# FPGA_2_MICS_SUP.net
KiCad netlist of a schematic drawn in Altium Designer
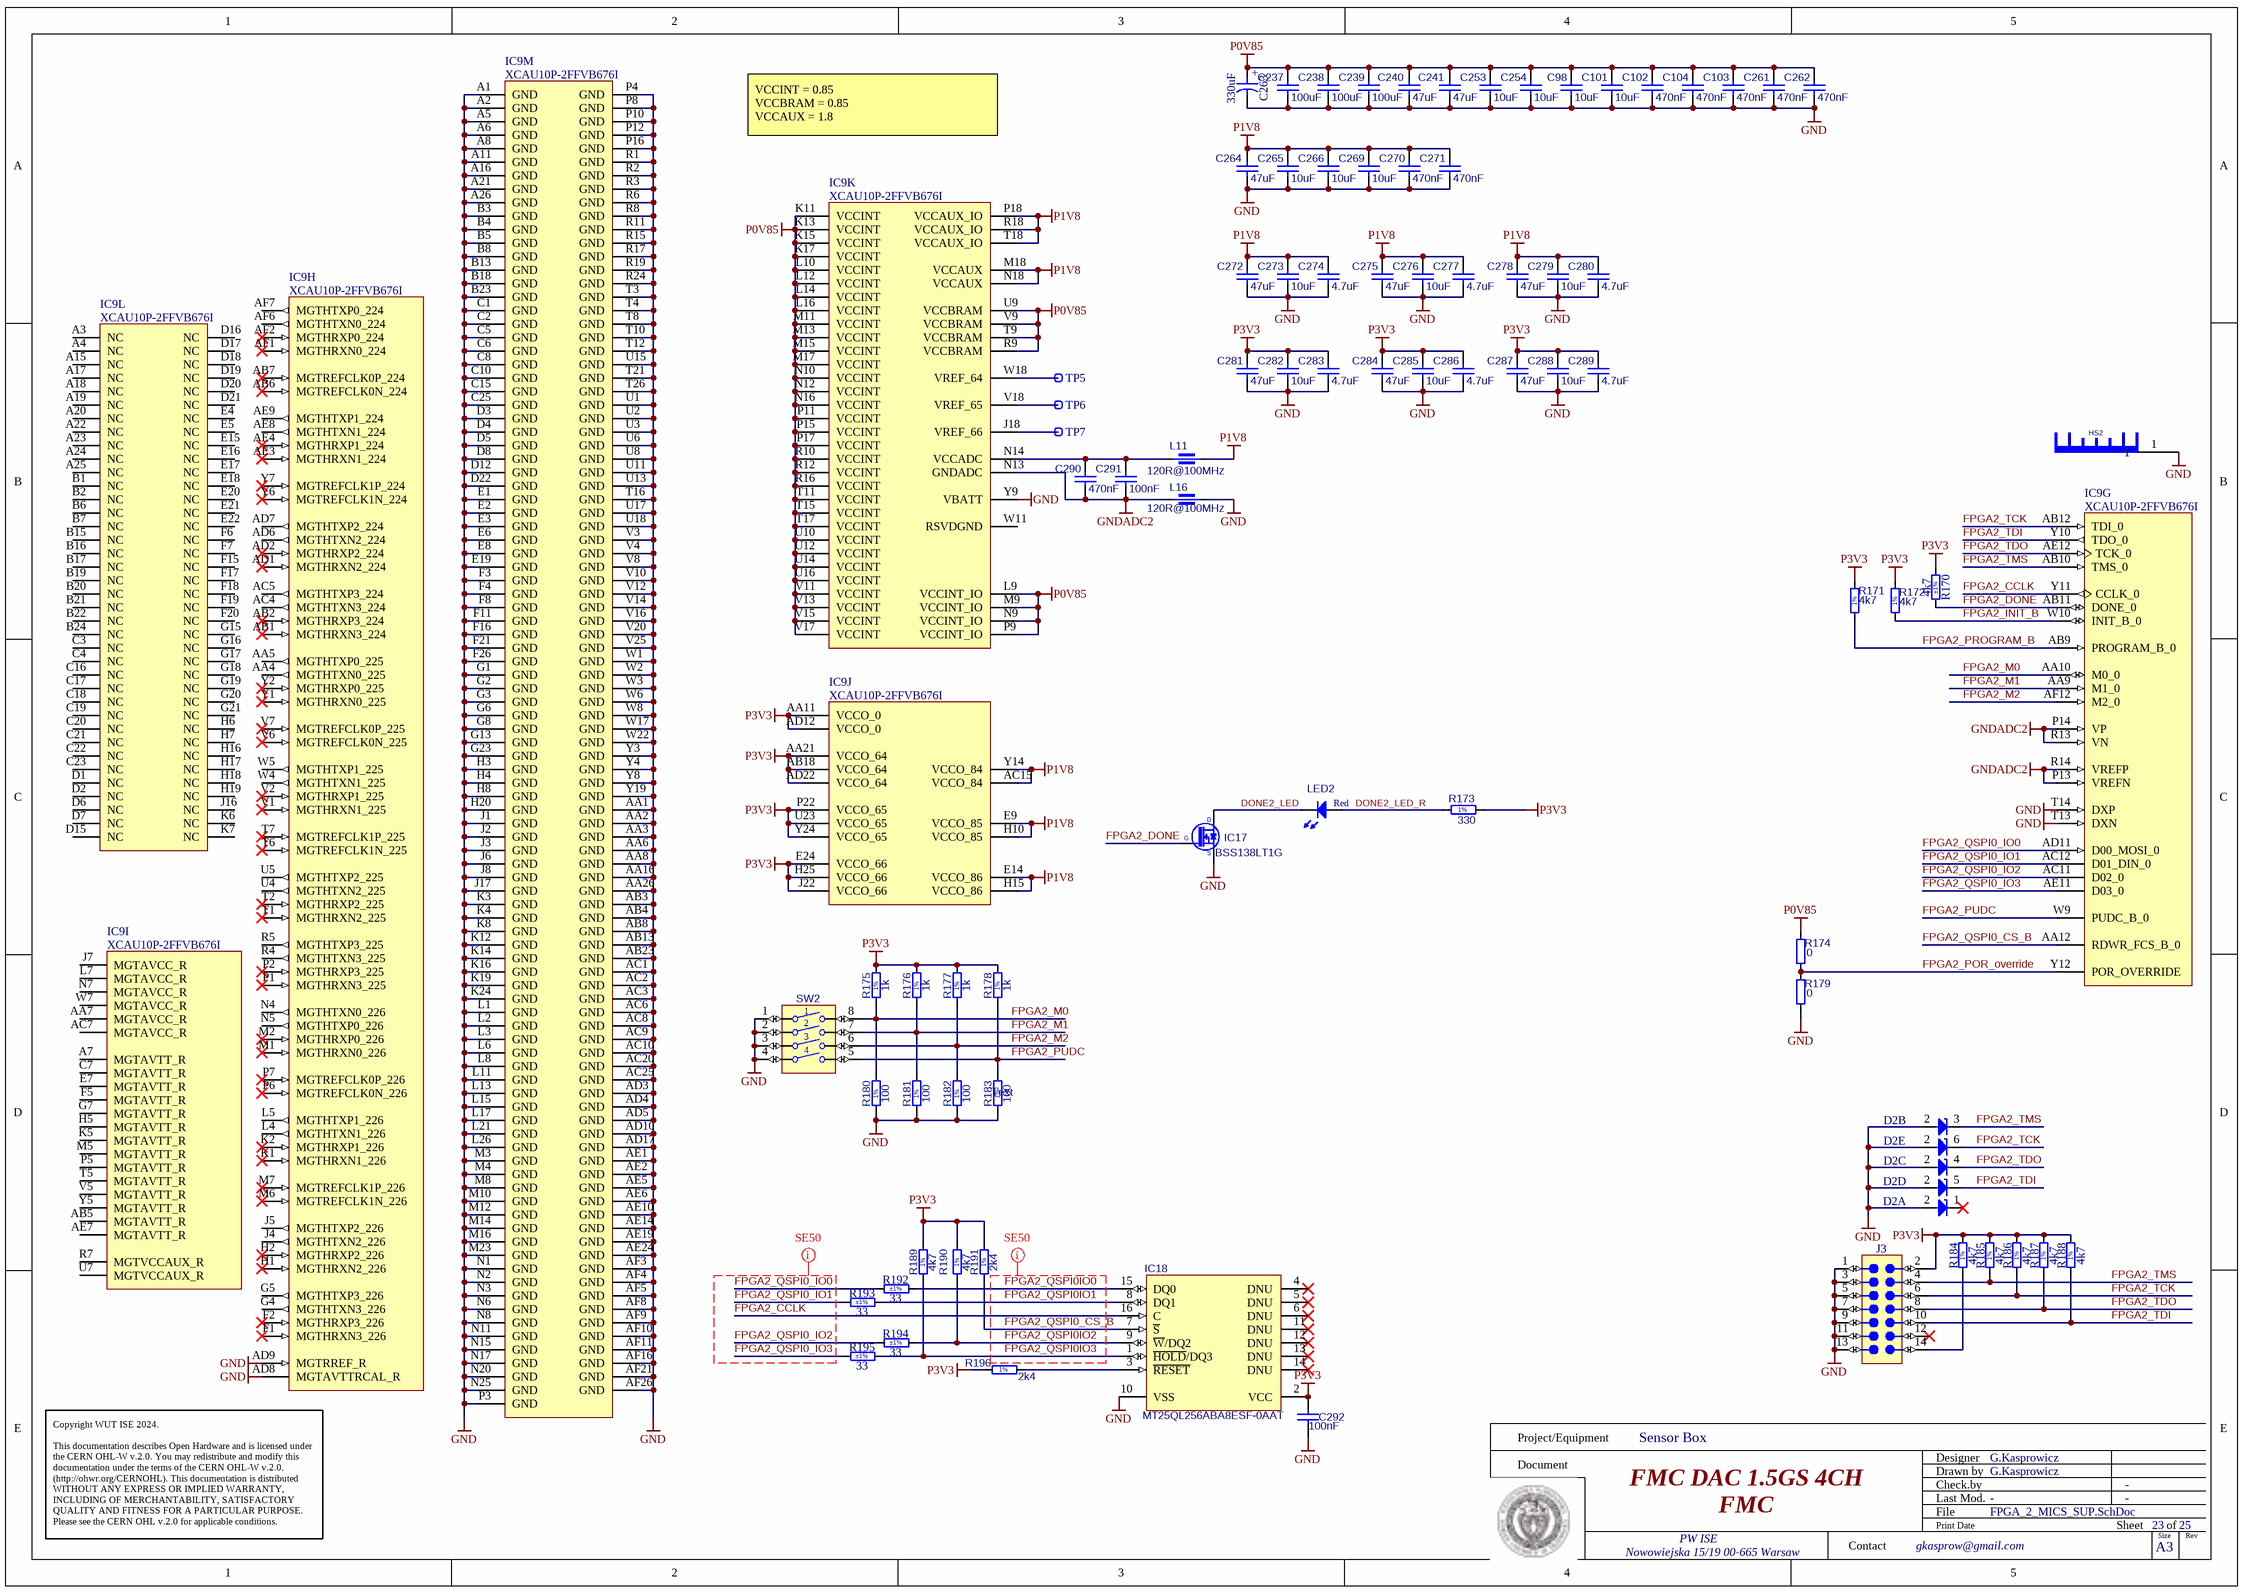
[diagram p0: FPGA_2_MICS_SUP.SchDoc]

(export (version "E")
  (design (tool "Eeschema 10.0.6"))
  (components
    (comp (ref "C98")
      (value "10uF")
      (footprint "CAPC1005X70N")
      (description "Non-polarised capacitor")
      (fields
        (field (name "PART NUMBER") "CC0402_10UF_6.3V_20%_X5R")
        (field (name "VOLTAGE") "6.3V")
        (field (name "AUTHOR") "CERN DEM JLC")
      )
      (libsource (lib "Capacitors") (part "Capacitor - non polarized"))
    )
    (comp (ref "C101")
      (value "10uF")
      (footprint "CAPC1005X70N")
      (description "Non-polarised capacitor")
      (fields
        (field (name "PART NUMBER") "CC0402_10UF_6.3V_20%_X5R")
        (field (name "VOLTAGE") "6.3V")
        (field (name "AUTHOR") "CERN DEM JLC")
      )
      (libsource (lib "Capacitors") (part "Capacitor - non polarized"))
    )
    (comp (ref "C102")
      (value "470nF")
      (footprint "CAPC0603X33N")
      (description "Non-polarised capacitor")
      (fields
        (field (name "PART NUMBER") "CC0201_470NF_4V_20%_X5R")
        (field (name "VOLTAGE") "4V")
        (field (name "AUTHOR") "CERN DEM JLC")
      )
      (libsource (lib "Capacitors") (part "Capacitor - non polarized"))
    )
    (comp (ref "C103")
      (value "470nF")
      (footprint "CAPC0603X33N")
      (description "Non-polarised capacitor")
      (fields
        (field (name "PART NUMBER") "CC0201_470NF_4V_20%_X5R")
        (field (name "VOLTAGE") "4V")
        (field (name "AUTHOR") "CERN DEM JLC")
      )
      (libsource (lib "Capacitors") (part "Capacitor - non polarized"))
    )
    (comp (ref "C104")
      (value "470nF")
      (footprint "CAPC0603X33N")
      (description "Non-polarised capacitor")
      (fields
        (field (name "PART NUMBER") "CC0201_470NF_4V_20%_X5R")
        (field (name "VOLTAGE") "4V")
        (field (name "AUTHOR") "CERN DEM JLC")
      )
      (libsource (lib "Capacitors") (part "Capacitor - non polarized"))
    )
    (comp (ref "C237")
      (value "100uF")
      (footprint "CAPC2013X145N")
      (description "Non-polarised capacitor")
      (fields
        (field (name "PART NUMBER") "CC0805_100UF_4V_20%_X6S_MURATA_GRM21BC80G107ME15")
        (field (name "VOLTAGE") "4V")
        (field (name "AUTHOR") "CERN DEM BC")
      )
      (libsource (lib "Capacitors") (part "Capacitor - non polarized"))
    )
    (comp (ref "C238")
      (value "100uF")
      (footprint "CAPC2013X145N")
      (description "Non-polarised capacitor")
      (fields
        (field (name "PART NUMBER") "CC0805_100UF_4V_20%_X6S_MURATA_GRM21BC80G107ME15")
        (field (name "VOLTAGE") "4V")
        (field (name "AUTHOR") "CERN DEM BC")
      )
      (libsource (lib "Capacitors") (part "Capacitor - non polarized"))
    )
    (comp (ref "C239")
      (value "100uF")
      (footprint "CAPC2013X145N")
      (description "Non-polarised capacitor")
      (fields
        (field (name "PART NUMBER") "CC0805_100UF_4V_20%_X6S_MURATA_GRM21BC80G107ME15")
        (field (name "VOLTAGE") "4V")
        (field (name "AUTHOR") "CERN DEM BC")
      )
      (libsource (lib "Capacitors") (part "Capacitor - non polarized"))
    )
    (comp (ref "C240")
      (value "47uF")
      (footprint "CAPC1608X100N")
      (description "Non-polarised capacitor")
      (fields
        (field (name "PART NUMBER") "CC0603_47UF_2.5V_20%_X6S_MURATA_GRM188C80E476ME05")
        (field (name "VOLTAGE") "2.5V")
        (field (name "AUTHOR") "CERN DEM BC")
      )
      (libsource (lib "Capacitors") (part "Capacitor - non polarized"))
    )
    (comp (ref "C241")
      (value "47uF")
      (footprint "CAPC1608X100N")
      (description "Non-polarised capacitor")
      (fields
        (field (name "PART NUMBER") "CC0603_47UF_2.5V_20%_X6S_MURATA_GRM188C80E476ME05")
        (field (name "VOLTAGE") "2.5V")
        (field (name "AUTHOR") "CERN DEM BC")
      )
      (libsource (lib "Capacitors") (part "Capacitor - non polarized"))
    )
    (comp (ref "C253")
      (value "10uF")
      (footprint "CAPC1005X70N")
      (description "Non-polarised capacitor")
      (fields
        (field (name "PART NUMBER") "CC0402_10UF_6.3V_20%_X5R")
        (field (name "VOLTAGE") "6.3V")
        (field (name "AUTHOR") "CERN DEM JLC")
      )
      (libsource (lib "Capacitors") (part "Capacitor - non polarized"))
    )
    (comp (ref "C254")
      (value "10uF")
      (footprint "CAPC1005X70N")
      (description "Non-polarised capacitor")
      (fields
        (field (name "PART NUMBER") "CC0402_10UF_6.3V_20%_X5R")
        (field (name "VOLTAGE") "6.3V")
        (field (name "AUTHOR") "CERN DEM JLC")
      )
      (libsource (lib "Capacitors") (part "Capacitor - non polarized"))
    )
    (comp (ref "C261")
      (value "470nF")
      (footprint "CAPC0603X33N")
      (description "Non-polarised capacitor")
      (fields
        (field (name "PART NUMBER") "CC0201_470NF_4V_20%_X5R")
        (field (name "VOLTAGE") "4V")
        (field (name "AUTHOR") "CERN DEM JLC")
      )
      (libsource (lib "Capacitors") (part "Capacitor - non polarized"))
    )
    (comp (ref "C262")
      (value "470nF")
      (footprint "CAPC0603X33N")
      (description "Non-polarised capacitor")
      (fields
        (field (name "PART NUMBER") "CC0201_470NF_4V_20%_X5R")
        (field (name "VOLTAGE") "4V")
        (field (name "AUTHOR") "CERN DEM JLC")
      )
      (libsource (lib "Capacitors") (part "Capacitor - non polarized"))
    )
    (comp (ref "C263")
      (value "330uF")
      (footprint "CAPMP7343X190N")
      (description "Polarised capacitor")
      (fields
        (field (name "PART NUMBER") "CTE7343-19_330UF_2.5V_20%_LESR0009_KEMET_T520")
        (field (name "VOLTAGE") "2.5V")
        (field (name "AUTHOR") "CERN DEM HF")
      )
      (libsource (lib "Capacitors") (part "Capacitor - polarized"))
    )
    (comp (ref "C264")
      (value "47uF")
      (footprint "CAPC1608X100N")
      (description "Non-polarised capacitor")
      (fields
        (field (name "PART NUMBER") "CC0603_47UF_2.5V_20%_X6S_MURATA_GRM188C80E476ME05")
        (field (name "VOLTAGE") "2.5V")
        (field (name "AUTHOR") "CERN DEM BC")
      )
      (libsource (lib "Capacitors") (part "Capacitor - non polarized"))
    )
    (comp (ref "C265")
      (value "10uF")
      (footprint "CAPC1005X70N")
      (description "Non-polarised capacitor")
      (fields
        (field (name "PART NUMBER") "CC0402_10UF_6.3V_20%_X5R")
        (field (name "VOLTAGE") "6.3V")
        (field (name "AUTHOR") "CERN DEM JLC")
      )
      (libsource (lib "Capacitors") (part "Capacitor - non polarized"))
    )
    (comp (ref "C266")
      (value "10uF")
      (footprint "CAPC1005X70N")
      (description "Non-polarised capacitor")
      (fields
        (field (name "PART NUMBER") "CC0402_10UF_6.3V_20%_X5R")
        (field (name "VOLTAGE") "6.3V")
        (field (name "AUTHOR") "CERN DEM JLC")
      )
      (libsource (lib "Capacitors") (part "Capacitor - non polarized"))
    )
    (comp (ref "C269")
      (value "10uF")
      (footprint "CAPC1005X70N")
      (description "Non-polarised capacitor")
      (fields
        (field (name "PART NUMBER") "CC0402_10UF_6.3V_20%_X5R")
        (field (name "VOLTAGE") "6.3V")
        (field (name "AUTHOR") "CERN DEM JLC")
      )
      (libsource (lib "Capacitors") (part "Capacitor - non polarized"))
    )
    (comp (ref "C270")
      (value "470nF")
      (footprint "CAPC0603X33N")
      (description "Non-polarised capacitor")
      (fields
        (field (name "PART NUMBER") "CC0201_470NF_4V_20%_X5R")
        (field (name "VOLTAGE") "4V")
        (field (name "AUTHOR") "CERN DEM JLC")
      )
      (libsource (lib "Capacitors") (part "Capacitor - non polarized"))
    )
    (comp (ref "C271")
      (value "470nF")
      (footprint "CAPC0603X33N")
      (description "Non-polarised capacitor")
      (fields
        (field (name "PART NUMBER") "CC0201_470NF_4V_20%_X5R")
        (field (name "VOLTAGE") "4V")
        (field (name "AUTHOR") "CERN DEM JLC")
      )
      (libsource (lib "Capacitors") (part "Capacitor - non polarized"))
    )
    (comp (ref "C272")
      (value "47uF")
      (footprint "CAPC1608X100N")
      (description "Non-polarised capacitor")
      (fields
        (field (name "PART NUMBER") "CC0603_47UF_6.3V_20%_X5R")
        (field (name "VOLTAGE") "6.3V")
        (field (name "AUTHOR") "CERN DEM JLC")
      )
      (libsource (lib "Capacitors") (part "Capacitor - non polarized"))
    )
    (comp (ref "C273")
      (value "10uF")
      (footprint "CAPC1005X70N")
      (description "Non-polarised capacitor")
      (fields
        (field (name "PART NUMBER") "CC0402_10UF_6.3V_20%_X5R")
        (field (name "VOLTAGE") "6.3V")
        (field (name "AUTHOR") "CERN DEM JLC")
      )
      (libsource (lib "Capacitors") (part "Capacitor - non polarized"))
    )
    (comp (ref "C274")
      (value "4.7uF")
      (footprint "CAPC1005X61N")
      (description "Non-polarised capacitor")
      (fields
        (field (name "PART NUMBER") "CC0402_4.7UF_4V_20%_X6S_TDK_C1005X6S0G475M050BC")
        (field (name "VOLTAGE") "4V")
        (field (name "AUTHOR") "CERN DEM BC")
      )
      (libsource (lib "Capacitors") (part "Capacitor - non polarized"))
    )
    (comp (ref "C275")
      (value "47uF")
      (footprint "CAPC1608X100N")
      (description "Non-polarised capacitor")
      (fields
        (field (name "PART NUMBER") "CC0603_47UF_6.3V_20%_X5R")
        (field (name "VOLTAGE") "6.3V")
        (field (name "AUTHOR") "CERN DEM JLC")
      )
      (libsource (lib "Capacitors") (part "Capacitor - non polarized"))
    )
    (comp (ref "C276")
      (value "10uF")
      (footprint "CAPC1005X70N")
      (description "Non-polarised capacitor")
      (fields
        (field (name "PART NUMBER") "CC0402_10UF_6.3V_20%_X5R")
        (field (name "VOLTAGE") "6.3V")
        (field (name "AUTHOR") "CERN DEM JLC")
      )
      (libsource (lib "Capacitors") (part "Capacitor - non polarized"))
    )
    (comp (ref "C277")
      (value "4.7uF")
      (footprint "CAPC1005X61N")
      (description "Non-polarised capacitor")
      (fields
        (field (name "PART NUMBER") "CC0402_4.7UF_4V_20%_X6S_TDK_C1005X6S0G475M050BC")
        (field (name "VOLTAGE") "4V")
        (field (name "AUTHOR") "CERN DEM BC")
      )
      (libsource (lib "Capacitors") (part "Capacitor - non polarized"))
    )
    (comp (ref "C278")
      (value "47uF")
      (footprint "CAPC1608X100N")
      (description "Non-polarised capacitor")
      (fields
        (field (name "PART NUMBER") "CC0603_47UF_6.3V_20%_X5R")
        (field (name "VOLTAGE") "6.3V")
        (field (name "AUTHOR") "CERN DEM JLC")
      )
      (libsource (lib "Capacitors") (part "Capacitor - non polarized"))
    )
    (comp (ref "C279")
      (value "10uF")
      (footprint "CAPC1005X70N")
      (description "Non-polarised capacitor")
      (fields
        (field (name "PART NUMBER") "CC0402_10UF_6.3V_20%_X5R")
        (field (name "VOLTAGE") "6.3V")
        (field (name "AUTHOR") "CERN DEM JLC")
      )
      (libsource (lib "Capacitors") (part "Capacitor - non polarized"))
    )
    (comp (ref "C280")
      (value "4.7uF")
      (footprint "CAPC1005X61N")
      (description "Non-polarised capacitor")
      (fields
        (field (name "PART NUMBER") "CC0402_4.7UF_4V_20%_X6S_TDK_C1005X6S0G475M050BC")
        (field (name "VOLTAGE") "4V")
        (field (name "AUTHOR") "CERN DEM BC")
      )
      (libsource (lib "Capacitors") (part "Capacitor - non polarized"))
    )
    (comp (ref "C281")
      (value "47uF")
      (footprint "CAPC1608X100N")
      (description "Non-polarised capacitor")
      (fields
        (field (name "PART NUMBER") "CC0603_47UF_6.3V_20%_X5R")
        (field (name "VOLTAGE") "6.3V")
        (field (name "AUTHOR") "CERN DEM JLC")
      )
      (libsource (lib "Capacitors") (part "Capacitor - non polarized"))
    )
    (comp (ref "C282")
      (value "10uF")
      (footprint "CAPC1005X70N")
      (description "Non-polarised capacitor")
      (fields
        (field (name "PART NUMBER") "CC0402_10UF_6.3V_20%_X5R")
        (field (name "VOLTAGE") "6.3V")
        (field (name "AUTHOR") "CERN DEM JLC")
      )
      (libsource (lib "Capacitors") (part "Capacitor - non polarized"))
    )
    (comp (ref "C283")
      (value "4.7uF")
      (footprint "CAPC1005X61N")
      (description "Non-polarised capacitor")
      (fields
        (field (name "PART NUMBER") "CC0402_4.7UF_4V_20%_X6S_TDK_C1005X6S0G475M050BC")
        (field (name "VOLTAGE") "4V")
        (field (name "AUTHOR") "CERN DEM BC")
      )
      (libsource (lib "Capacitors") (part "Capacitor - non polarized"))
    )
    (comp (ref "C284")
      (value "47uF")
      (footprint "CAPC1608X100N")
      (description "Non-polarised capacitor")
      (fields
        (field (name "PART NUMBER") "CC0603_47UF_6.3V_20%_X5R")
        (field (name "VOLTAGE") "6.3V")
        (field (name "AUTHOR") "CERN DEM JLC")
      )
      (libsource (lib "Capacitors") (part "Capacitor - non polarized"))
    )
    (comp (ref "C285")
      (value "10uF")
      (footprint "CAPC1005X70N")
      (description "Non-polarised capacitor")
      (fields
        (field (name "PART NUMBER") "CC0402_10UF_6.3V_20%_X5R")
        (field (name "VOLTAGE") "6.3V")
        (field (name "AUTHOR") "CERN DEM JLC")
      )
      (libsource (lib "Capacitors") (part "Capacitor - non polarized"))
    )
    (comp (ref "C286")
      (value "4.7uF")
      (footprint "CAPC1005X61N")
      (description "Non-polarised capacitor")
      (fields
        (field (name "PART NUMBER") "CC0402_4.7UF_4V_20%_X6S_TDK_C1005X6S0G475M050BC")
        (field (name "VOLTAGE") "4V")
        (field (name "AUTHOR") "CERN DEM BC")
      )
      (libsource (lib "Capacitors") (part "Capacitor - non polarized"))
    )
    (comp (ref "C287")
      (value "47uF")
      (footprint "CAPC1608X100N")
      (description "Non-polarised capacitor")
      (fields
        (field (name "PART NUMBER") "CC0603_47UF_6.3V_20%_X5R")
        (field (name "VOLTAGE") "6.3V")
        (field (name "AUTHOR") "CERN DEM JLC")
      )
      (libsource (lib "Capacitors") (part "Capacitor - non polarized"))
    )
    (comp (ref "C288")
      (value "10uF")
      (footprint "CAPC1005X70N")
      (description "Non-polarised capacitor")
      (fields
        (field (name "PART NUMBER") "CC0402_10UF_6.3V_20%_X5R")
        (field (name "VOLTAGE") "6.3V")
        (field (name "AUTHOR") "CERN DEM JLC")
      )
      (libsource (lib "Capacitors") (part "Capacitor - non polarized"))
    )
    (comp (ref "C289")
      (value "4.7uF")
      (footprint "CAPC1005X61N")
      (description "Non-polarised capacitor")
      (fields
        (field (name "PART NUMBER") "CC0402_4.7UF_4V_20%_X6S_TDK_C1005X6S0G475M050BC")
        (field (name "VOLTAGE") "4V")
        (field (name "AUTHOR") "CERN DEM BC")
      )
      (libsource (lib "Capacitors") (part "Capacitor - non polarized"))
    )
    (comp (ref "C290")
      (value "470nF")
      (footprint "CAPC1005X55N")
      (description "Non-polarised capacitor")
      (fields
        (field (name "PART NUMBER") "CC0402_470NF_16V_10%_X5R")
        (field (name "VOLTAGE") "16V")
        (field (name "AUTHOR") "CERN DEM JLC")
      )
      (libsource (lib "Capacitors") (part "Capacitor - non polarized"))
    )
    (comp (ref "C291")
      (value "100nF")
      (footprint "CAPC0603X33N")
      (description "Non-polarised capacitor")
      (fields
        (field (name "MANUFACTURER PART NUMBER") "CC0201_100NF_6.3V_10%_X5R")
        (field (name "MANUFACTURER") "GENERIC")
        (field (name "AUTHOR") "CERN DEM JLC")
      )
      (libsource (lib "Capacitors") (part "Capacitor - non polarized"))
    )
    (comp (ref "C292")
      (value "100nF")
      (footprint "CAPC0603X33N")
      (description "Non-polarised capacitor")
      (fields
        (field (name "MANUFACTURER PART NUMBER") "CC0201_100NF_6.3V_10%_X5R")
        (field (name "MANUFACTURER") "GENERIC")
        (field (name "AUTHOR") "CERN DEM JLC")
      )
      (libsource (lib "Capacitors") (part "Capacitor - non polarized"))
    )
    (comp (ref "D2")
      (value "PESD3V3L5UY")
      (footprint "SOT65P210X110-6N")
      (description "Fivefold ESD Protection Diode Arrays")
      (fields
        (field (name "VOLTAGE") "3.3V")
        (field (name "POWER") "200W")
        (field (name "AUTHOR") "CERN DEM WB")
      )
      (libsource (lib "ICs And Semiconductors") (part "PESD Array 5diodes 6pins Common anode2"))
    )
    (comp (ref "HS2")
      (value "Heat Sink No Pad")
      (footprint "HSINK_WAKEFIELD_SKV585811-CU")
      (description "Heat Sink Without Pad")
      (fields
        (field (name "PART NUMBER") "HSINK_WAKEFIELD_SKV585811-CU")
        (field (name "MANUFACTURER") "WAKEFIELD-VETTE")
        (field (name "AUTHOR") "CERN DEM JMW")
      )
      (libsource (lib "Eletro-mechanical") (part "Heat Sink No Pad"))
    )
    (comp (ref "IC9")
      (value "XCAU10P-2FFVB676I")
      (footprint "BGA676C100P26X26_2700X2700X350")
      (description "Artix UltraScale + Field Programmable Gate Array (FPGA), 676-Pin BGA, Industrial Grade")
      (fields (field (name "MANUFACTURER") "AMD") (field (name "AUTHOR") "CERN DEM HF"))
      (libsource (lib "ICs And Semiconductors") (part "XCAU10P-2FFVB676I"))
    )
    (comp (ref "IC17")
      (value "BSS138LT1G")
      (footprint "SOT95P240X110-3N")
      (description "N-CHANNEL MOSFET WITH DIODE")
      (fields (field (name "MANUFACTURER") "ON SEMICONDUCTOR") (field (name "AUTHOR") "CERN DEM JLC"))
      (libsource (lib "ICs And Semiconductors") (part "N-MOSFET-D 1G 2S 3D"))
    )
    (comp (ref "IC18")
      (value "MT25QL256ABA8ESF-0AAT")
      (footprint "SOIC127P1030X265-16N")
      (description "256Mbit (32MB), 2.7V-3.6V, Multiple I/O Serial NOR Flash Memory,with Reset# & Hold#")
      (fields (field (name "MANUFACTURER") "MICRON TECHNOLOGY") (field (name "AUTHOR") "CERN DEM JLC"))
      (libsource (lib "ICs And Semiconductors") (part "MT25QL256ABA8ESF"))
    )
    (comp (ref "J3")
      (value "~")
      (footprint "MOLEX_87832-1420")
      (description "Connector 14 Male")
      (fields
        (field (name "PART NUMBER") "MOLEX_87832-1420")
        (field (name "MANUFACTURER") "MOLEX")
        (field (name "AUTHOR") "CERN DEM JLC")
      )
      (libsource (lib "Connectors") (part "Connector 14 Male"))
    )
    (comp (ref "L11")
      (value "120R@100MHz")
      (footprint "INDC1608X95N")
      (fields
        (field (name "PART NUMBER") "IND0603_MURATA_BLM18PG121SN1D")
        (field (name "POWER") "2A")
        (field (name "MANUFACTURER") "MURATA")
        (field (name "AUTHOR") "CERN DEM BC")
      )
      (libsource (lib "Inductors & Transformers") (part "Ferrite Bead"))
    )
    (comp (ref "L16")
      (value "120R@100MHz")
      (footprint "INDC1608X95N")
      (fields
        (field (name "PART NUMBER") "IND0603_MURATA_BLM18PG121SN1D")
        (field (name "POWER") "2A")
        (field (name "MANUFACTURER") "MURATA")
        (field (name "AUTHOR") "CERN DEM BC")
      )
      (libsource (lib "Inductors & Transformers") (part "Ferrite Bead"))
    )
    (comp (ref "LED2")
      (value "Red")
      (footprint "LED_KINGBRIGHT_KPH-1608SURCK")
      (description "LED Red 1C 2A")
      (fields
        (field (name "PART NUMBER") "LED_KINGBRIGHT_KPH-1608SURCK")
        (field (name "MANUFACTURER") "KINGBRIGHT")
        (field (name "AUTHOR") "CERN DEM JLC")
      )
      (libsource (lib "ICs And Semiconductors") (part "LED Red 1C 2A"))
    )
    (comp (ref "R170")
      (value "4k7")
      (footprint "RESC1005X40N")
      (description "Resistor - 1%")
      (fields
        (field (name "TOLERANCE") "±1%")
        (field (name "PART NUMBER") "R0402_4K7_1%_0.0625W_100PPM")
        (field (name "POWER") "0.0625W")
        (field (name "AUTHOR") "CERN DEM JLC")
      )
      (libsource (lib "Resistors") (part "Resistor - 1%"))
    )
    (comp (ref "R171")
      (value "4k7")
      (footprint "RESC1005X40N")
      (description "Resistor - 1%")
      (fields
        (field (name "MANUFACTURER PART NUMBER") "R0402_4K7_1%_0.0625W_100PPM")
        (field (name "MANUFACTURER") "GENERIC")
        (field (name "AUTHOR") "CERN DEM JLC")
      )
      (libsource (lib "Resistors") (part "Resistor - 1%"))
    )
    (comp (ref "R172")
      (value "4k7")
      (footprint "RESC1005X40N")
      (description "Resistor - 1%")
      (fields
        (field (name "MANUFACTURER PART NUMBER") "R0402_4K7_1%_0.0625W_100PPM")
        (field (name "MANUFACTURER") "GENERIC")
        (field (name "AUTHOR") "CERN DEM JLC")
      )
      (libsource (lib "Resistors") (part "Resistor - 1%"))
    )
    (comp (ref "R173")
      (value "330")
      (footprint "RESC1005X40N")
      (description "Resistor - 1%")
      (fields
        (field (name "PART NUMBER") "R0402_330R_1%_0.0625W_100PPM")
        (field (name "POWER") "0.0625W")
        (field (name "AUTHOR") "CERN DEM JLC")
      )
      (libsource (lib "Resistors") (part "Resistor - 1%"))
    )
    (comp (ref "R174")
      (value "0")
      (footprint "RESC1005X40N")
      (description "Resistor")
      (fields
        (field (name "MANUFACTURER PART NUMBER") "R0402_0R_JUMPER")
        (field (name "MANUFACTURER") "GENERIC")
        (field (name "AUTHOR") "CERN DEM JLC")
      )
      (libsource (lib "Resistors") (part "Resistor"))
    )
    (comp (ref "R175")
      (value "1k")
      (footprint "RESC1005X40N")
      (description "Resistor - 1%")
      (fields
        (field (name "PART NUMBER") "R0402_1K_1%_0.0625W_100PPM")
        (field (name "POWER") "0.0625W")
        (field (name "AUTHOR") "CERN DEM JLC")
      )
      (libsource (lib "Resistors") (part "Resistor - 1%"))
    )
    (comp (ref "R176")
      (value "1k")
      (footprint "RESC1005X40N")
      (description "Resistor - 1%")
      (fields
        (field (name "PART NUMBER") "R0402_1K_1%_0.0625W_100PPM")
        (field (name "POWER") "0.0625W")
        (field (name "AUTHOR") "CERN DEM JLC")
      )
      (libsource (lib "Resistors") (part "Resistor - 1%"))
    )
    (comp (ref "R177")
      (value "1k")
      (footprint "RESC1005X40N")
      (description "Resistor - 1%")
      (fields
        (field (name "PART NUMBER") "R0402_1K_1%_0.0625W_100PPM")
        (field (name "POWER") "0.0625W")
        (field (name "AUTHOR") "CERN DEM JLC")
      )
      (libsource (lib "Resistors") (part "Resistor - 1%"))
    )
    (comp (ref "R178")
      (value "1k")
      (footprint "RESC1005X40N")
      (description "Resistor - 1%")
      (fields
        (field (name "PART NUMBER") "R0402_1K_1%_0.0625W_100PPM")
        (field (name "POWER") "0.0625W")
        (field (name "AUTHOR") "CERN DEM JLC")
      )
      (libsource (lib "Resistors") (part "Resistor - 1%"))
    )
    (comp (ref "R179")
      (value "0")
      (footprint "RESC1005X40N")
      (description "Resistor")
      (fields
        (field (name "MANUFACTURER PART NUMBER") "R0402_0R_JUMPER")
        (field (name "MANUFACTURER") "GENERIC")
        (field (name "AUTHOR") "CERN DEM JLC")
      )
      (libsource (lib "Resistors") (part "Resistor"))
    )
    (comp (ref "R180")
      (value "100")
      (footprint "RESC1005X40N")
      (description "Resistor - 1%")
      (fields
        (field (name "PART NUMBER") "R0402_100R_1%_0.0625W_100PPM")
        (field (name "POWER") "0.0625W")
        (field (name "AUTHOR") "CERN DEM JLC")
      )
      (libsource (lib "Resistors") (part "Resistor - 1%"))
    )
    (comp (ref "R181")
      (value "100")
      (footprint "RESC1005X40N")
      (description "Resistor - 1%")
      (fields
        (field (name "PART NUMBER") "R0402_100R_1%_0.0625W_100PPM")
        (field (name "POWER") "0.0625W")
        (field (name "AUTHOR") "CERN DEM JLC")
      )
      (libsource (lib "Resistors") (part "Resistor - 1%"))
    )
    (comp (ref "R182")
      (value "100")
      (footprint "RESC1005X40N")
      (description "Resistor - 1%")
      (fields
        (field (name "PART NUMBER") "R0402_100R_1%_0.0625W_100PPM")
        (field (name "POWER") "0.0625W")
        (field (name "AUTHOR") "CERN DEM JLC")
      )
      (libsource (lib "Resistors") (part "Resistor - 1%"))
    )
    (comp (ref "R183")
      (value "100")
      (footprint "RESC1005X40N")
      (description "Resistor - 1%")
      (fields
        (field (name "PART NUMBER") "R0402_100R_1%_0.0625W_100PPM")
        (field (name "POWER") "0.0625W")
        (field (name "AUTHOR") "CERN DEM JLC")
      )
      (libsource (lib "Resistors") (part "Resistor - 1%"))
    )
    (comp (ref "R184")
      (value "4k7")
      (footprint "RESC1005X40N")
      (description "Resistor - 1%")
      (fields
        (field (name "PART NUMBER") "R0402_4K7_1%_0.0625W_100PPM")
        (field (name "POWER") "0.0625W")
        (field (name "AUTHOR") "CERN DEM JLC")
      )
      (libsource (lib "Resistors") (part "Resistor - 1%"))
    )
    (comp (ref "R185")
      (value "4k7")
      (footprint "RESC1005X40N")
      (description "Resistor - 1%")
      (fields
        (field (name "PART NUMBER") "R0402_4K7_1%_0.0625W_100PPM")
        (field (name "POWER") "0.0625W")
        (field (name "AUTHOR") "CERN DEM JLC")
      )
      (libsource (lib "Resistors") (part "Resistor - 1%"))
    )
    (comp (ref "R186")
      (value "4k7")
      (footprint "RESC1005X40N")
      (description "Resistor - 1%")
      (fields
        (field (name "PART NUMBER") "R0402_4K7_1%_0.0625W_100PPM")
        (field (name "POWER") "0.0625W")
        (field (name "AUTHOR") "CERN DEM JLC")
      )
      (libsource (lib "Resistors") (part "Resistor - 1%"))
    )
    (comp (ref "R187")
      (value "4k7")
      (footprint "RESC1005X40N")
      (description "Resistor - 1%")
      (fields
        (field (name "PART NUMBER") "R0402_4K7_1%_0.0625W_100PPM")
        (field (name "POWER") "0.0625W")
        (field (name "AUTHOR") "CERN DEM JLC")
      )
      (libsource (lib "Resistors") (part "Resistor - 1%"))
    )
    (comp (ref "R188")
      (value "4k7")
      (footprint "RESC1005X40N")
      (description "Resistor - 1%")
      (fields
        (field (name "PART NUMBER") "R0402_4K7_1%_0.0625W_100PPM")
        (field (name "POWER") "0.0625W")
        (field (name "AUTHOR") "CERN DEM JLC")
      )
      (libsource (lib "Resistors") (part "Resistor - 1%"))
    )
    (comp (ref "R189")
      (value "4k7")
      (footprint "RESC1005X40N")
      (description "Resistor - 1%")
      (fields
        (field (name "MANUFACTURER PART NUMBER") "R0402_4K7_1%_0.0625W_100PPM")
        (field (name "MANUFACTURER") "GENERIC")
        (field (name "AUTHOR") "CERN DEM JLC")
      )
      (libsource (lib "Resistors") (part "Resistor - 1%"))
    )
    (comp (ref "R190")
      (value "4k7")
      (footprint "RESC1005X40N")
      (description "Resistor - 1%")
      (fields
        (field (name "MANUFACTURER PART NUMBER") "R0402_4K7_1%_0.0625W_100PPM")
        (field (name "MANUFACTURER") "GENERIC")
        (field (name "AUTHOR") "CERN DEM JLC")
      )
      (libsource (lib "Resistors") (part "Resistor - 1%"))
    )
    (comp (ref "R191")
      (value "2k4")
      (footprint "RESC1005X40N")
      (description "Resistor - 1%")
      (fields
        (field (name "MANUFACTURER PART NUMBER") "R0402_2K4_1%_0.0625W_100PPM")
        (field (name "MANUFACTURER") "GENERIC")
        (field (name "AUTHOR") "CERN DEM JLC")
      )
      (libsource (lib "Resistors") (part "Resistor - 1%"))
    )
    (comp (ref "R192")
      (value "33")
      (footprint "RESC1005X40N")
      (description "Resistor - 1%")
      (fields
        (field (name "TOLERANCE") "±1%")
        (field (name "PART NUMBER") "R0402_33R_1%_0.0625W_100PPM")
        (field (name "POWER") "0.0625W")
        (field (name "AUTHOR") "CERN DEM JLC")
      )
      (libsource (lib "Resistors") (part "Resistor - 1%"))
    )
    (comp (ref "R193")
      (value "33")
      (footprint "RESC1005X40N")
      (description "Resistor - 1%")
      (fields
        (field (name "TOLERANCE") "±1%")
        (field (name "PART NUMBER") "R0402_33R_1%_0.0625W_100PPM")
        (field (name "POWER") "0.0625W")
        (field (name "AUTHOR") "CERN DEM JLC")
      )
      (libsource (lib "Resistors") (part "Resistor - 1%"))
    )
    (comp (ref "R194")
      (value "33")
      (footprint "RESC1005X40N")
      (description "Resistor - 1%")
      (fields
        (field (name "TOLERANCE") "±1%")
        (field (name "PART NUMBER") "R0402_33R_1%_0.0625W_100PPM")
        (field (name "POWER") "0.0625W")
        (field (name "AUTHOR") "CERN DEM JLC")
      )
      (libsource (lib "Resistors") (part "Resistor - 1%"))
    )
    (comp (ref "R195")
      (value "33")
      (footprint "RESC1005X40N")
      (description "Resistor - 1%")
      (fields
        (field (name "TOLERANCE") "±1%")
        (field (name "PART NUMBER") "R0402_33R_1%_0.0625W_100PPM")
        (field (name "POWER") "0.0625W")
        (field (name "AUTHOR") "CERN DEM JLC")
      )
      (libsource (lib "Resistors") (part "Resistor - 1%"))
    )
    (comp (ref "R196")
      (value "2k4")
      (footprint "RESC1005X40N")
      (description "Resistor - 1%")
      (fields
        (field (name "MANUFACTURER PART NUMBER") "R0402_2K4_1%_0.0625W_100PPM")
        (field (name "MANUFACTURER") "GENERIC")
        (field (name "AUTHOR") "CERN DEM JLC")
      )
      (libsource (lib "Resistors") (part "Resistor - 1%"))
    )
    (comp (ref "SW2")
      (value "Switch")
      (footprint "SW_TYCO_1571983-4")
      (description "4 Ways SPST DIP Switch")
      (fields
        (field (name "PART NUMBER") "SW_TYCO_1571983-4")
        (field (name "MANUFACTURER") "TYCO")
        (field (name "AUTHOR") "CERN DEM JLC")
      )
      (libsource (lib "Eletro-mechanical") (part "SW 4x SPST DIP Switch"))
    )
    (comp (ref "TP5")
      (value "Test Point")
      (footprint "TPS127")
      (fields (field (name "PART NUMBER") "SMD_PAD_1.27X1.27MM") (field (name "AUTHOR") "CERN DEM JLC"))
      (libsource (lib "Eletro-mechanical") (part "Test Point"))
    )
    (comp (ref "TP6")
      (value "Test Point")
      (footprint "TPS127")
      (fields (field (name "PART NUMBER") "SMD_PAD_1.27X1.27MM") (field (name "AUTHOR") "CERN DEM JLC"))
      (libsource (lib "Eletro-mechanical") (part "Test Point"))
    )
    (comp (ref "TP7")
      (value "Test Point")
      (footprint "TPS127")
      (fields (field (name "PART NUMBER") "SMD_PAD_1.27X1.27MM") (field (name "AUTHOR") "CERN DEM JLC"))
      (libsource (lib "Eletro-mechanical") (part "Test Point"))
    )
  )
  (nets
    (net (code "1") (name "/DONE2_LED") (class "Default")
      (node (ref "IC17") (pin "3") (pinfunction "D_3") (pintype "passive"))
      (node (ref "LED2") (pin "1") (pinfunction "C_1") (pintype "passive"))
    )
    (net (code "2") (name "/DONE2_LED_R") (class "Default")
      (node (ref "LED2") (pin "2") (pinfunction "A_2") (pintype "passive"))
      (node (ref "R173") (pin "1") (pinfunction "1_1") (pintype "passive"))
    )
    (net (code "3") (name "/FPGA2_CCLK") (class "Default")
      (node (ref "IC18") (pin "16") (pinfunction "C_16") (pintype "input"))
      (node (ref "IC9") (pin "Y11") (pinfunction "CCLK_0_Y11") (pintype "output"))
    )
    (net (code "4") (name "/FPGA2_DONE") (class "Default")
      (node (ref "IC17") (pin "1") (pinfunction "G_1") (pintype "passive"))
      (node (ref "IC9") (pin "AB11") (pinfunction "DONE_0_AB11") (pintype "bidirectional"))
      (node (ref "R170") (pin "1") (pinfunction "1_1") (pintype "passive"))
    )
    (net (code "5") (name "/FPGA2_INIT_B") (class "Default")
      (node (ref "IC9") (pin "W10") (pinfunction "INIT_B_0_W10") (pintype "bidirectional"))
      (node (ref "R172") (pin "1") (pinfunction "1_1") (pintype "passive"))
    )
    (net (code "6") (name "/FPGA2_M0") (class "Default")
      (node (ref "IC9") (pin "AA10") (pinfunction "M0_0_AA10") (pintype "bidirectional"))
      (node (ref "R175") (pin "1") (pinfunction "1_1") (pintype "passive"))
      (node (ref "R180") (pin "2") (pinfunction "2_2") (pintype "passive"))
      (node (ref "SW2") (pin "8") (pinfunction "8_8") (pintype "bidirectional"))
    )
    (net (code "7") (name "/FPGA2_M1") (class "Default")
      (node (ref "IC9") (pin "AA9") (pinfunction "M1_0_AA9") (pintype "input"))
      (node (ref "R176") (pin "1") (pinfunction "1_1") (pintype "passive"))
      (node (ref "R181") (pin "2") (pinfunction "2_2") (pintype "passive"))
      (node (ref "SW2") (pin "7") (pinfunction "7_7") (pintype "bidirectional"))
    )
    (net (code "8") (name "/FPGA2_M2") (class "Default")
      (node (ref "IC9") (pin "AF12") (pinfunction "M2_0_AF12") (pintype "input"))
      (node (ref "R177") (pin "1") (pinfunction "1_1") (pintype "passive"))
      (node (ref "R182") (pin "2") (pinfunction "2_2") (pintype "passive"))
      (node (ref "SW2") (pin "6") (pinfunction "6_6") (pintype "bidirectional"))
    )
    (net (code "9") (name "/FPGA2_POR_override") (class "Default")
      (node (ref "IC9") (pin "Y12") (pinfunction "POR_OVERRIDE_Y12") (pintype "passive"))
      (node (ref "R174") (pin "1") (pinfunction "1_1") (pintype "passive"))
      (node (ref "R179") (pin "2") (pinfunction "2_2") (pintype "passive"))
    )
    (net (code "10") (name "/FPGA2_PROGRAM_B") (class "Default")
      (node (ref "IC9") (pin "AB9") (pinfunction "PROGRAM_B_0_AB9") (pintype "input"))
      (node (ref "R171") (pin "1") (pinfunction "1_1") (pintype "passive"))
    )
    (net (code "11") (name "/FPGA2_PUDC") (class "Default")
      (node (ref "IC9") (pin "W9") (pinfunction "PUDC_B_0_W9") (pintype "passive"))
      (node (ref "R178") (pin "1") (pinfunction "1_1") (pintype "passive"))
      (node (ref "R183") (pin "2") (pinfunction "2_2") (pintype "passive"))
      (node (ref "SW2") (pin "5") (pinfunction "5_5") (pintype "bidirectional"))
    )
    (net (code "12") (name "/FPGA2_QSPI0IO0") (class "Default")
      (node (ref "IC18") (pin "15") (pinfunction "DQ0_15") (pintype "bidirectional"))
      (node (ref "R192") (pin "2") (pinfunction "2_2") (pintype "passive"))
    )
    (net (code "13") (name "/FPGA2_QSPI0IO1") (class "Default")
      (node (ref "IC18") (pin "8") (pinfunction "DQ1_8") (pintype "bidirectional"))
      (node (ref "R193") (pin "2") (pinfunction "2_2") (pintype "passive"))
    )
    (net (code "14") (name "/FPGA2_QSPI0IO2") (class "Default")
      (node (ref "IC18") (pin "9") (pinfunction "~{W}/DQ2_9") (pintype "bidirectional"))
      (node (ref "R190") (pin "1") (pinfunction "1_1") (pintype "passive"))
      (node (ref "R194") (pin "2") (pinfunction "2_2") (pintype "passive"))
    )
    (net (code "15") (name "/FPGA2_QSPI0IO3") (class "Default")
      (node (ref "IC18") (pin "1") (pinfunction "~{HOLD}/DQ3_1") (pintype "bidirectional"))
      (node (ref "R189") (pin "1") (pinfunction "1_1") (pintype "passive"))
      (node (ref "R195") (pin "2") (pinfunction "2_2") (pintype "passive"))
    )
    (net (code "16") (name "/FPGA2_QSPI0_CS_B") (class "Default")
      (node (ref "IC18") (pin "7") (pinfunction "~{S}_7") (pintype "input"))
      (node (ref "IC9") (pin "AA12") (pinfunction "RDWR_FCS_B_0_AA12") (pintype "passive"))
      (node (ref "R191") (pin "1") (pinfunction "1_1") (pintype "passive"))
    )
    (net (code "17") (name "/FPGA2_QSPI0_IO0") (class "Default")
      (node (ref "IC9") (pin "AD11") (pinfunction "D00_MOSI_0_AD11") (pintype "input"))
      (node (ref "R192") (pin "1") (pinfunction "1_1") (pintype "passive"))
    )
    (net (code "18") (name "/FPGA2_QSPI0_IO1") (class "Default")
      (node (ref "IC9") (pin "AC12") (pinfunction "D01_DIN_0_AC12") (pintype "passive"))
      (node (ref "R193") (pin "1") (pinfunction "1_1") (pintype "passive"))
    )
    (net (code "19") (name "/FPGA2_QSPI0_IO2") (class "Default")
      (node (ref "IC9") (pin "AC11") (pinfunction "D02_0_AC11") (pintype "passive"))
      (node (ref "R194") (pin "1") (pinfunction "1_1") (pintype "passive"))
    )
    (net (code "20") (name "/FPGA2_QSPI0_IO3") (class "Default")
      (node (ref "IC9") (pin "AE11") (pinfunction "D03_0_AE11") (pintype "passive"))
      (node (ref "R195") (pin "1") (pinfunction "1_1") (pintype "passive"))
    )
    (net (code "21") (name "/FPGA2_TCK") (class "Default")
      (node (ref "D2") (pin "6") (pinfunction "C_6") (pintype "passive"))
      (node (ref "IC9") (pin "AB12") (pinfunction "TDI_0_AB12") (pintype "input"))
      (node (ref "J3") (pin "6") (pinfunction "6_6") (pintype "bidirectional"))
      (node (ref "R186") (pin "1") (pinfunction "1_1") (pintype "passive"))
    )
    (net (code "22") (name "/FPGA2_TDI") (class "Default")
      (node (ref "D2") (pin "5") (pinfunction "C_5") (pintype "passive"))
      (node (ref "IC9") (pin "Y10") (pinfunction "TDO_0_Y10") (pintype "output"))
      (node (ref "J3") (pin "10") (pinfunction "10_10") (pintype "bidirectional"))
      (node (ref "R188") (pin "1") (pinfunction "1_1") (pintype "passive"))
    )
    (net (code "23") (name "/FPGA2_TDO") (class "Default")
      (node (ref "D2") (pin "4") (pinfunction "C_4") (pintype "passive"))
      (node (ref "IC9") (pin "AE12") (pinfunction "TCK_0_AE12") (pintype "input"))
      (node (ref "J3") (pin "8") (pinfunction "8_8") (pintype "bidirectional"))
      (node (ref "R187") (pin "1") (pinfunction "1_1") (pintype "passive"))
    )
    (net (code "24") (name "/FPGA2_TMS") (class "Default")
      (node (ref "D2") (pin "3") (pinfunction "C_3") (pintype "passive"))
      (node (ref "IC9") (pin "AB10") (pinfunction "TMS_0_AB10") (pintype "input"))
      (node (ref "J3") (pin "4") (pinfunction "4_4") (pintype "bidirectional"))
      (node (ref "R185") (pin "1") (pinfunction "1_1") (pintype "passive"))
    )
    (net (code "25") (name "GND") (class "Default")
      (node (ref "C101") (pin "1") (pinfunction "1_1") (pintype "passive"))
      (node (ref "C102") (pin "1") (pinfunction "1_1") (pintype "passive"))
      (node (ref "C103") (pin "1") (pinfunction "1_1") (pintype "passive"))
      (node (ref "C104") (pin "1") (pinfunction "1_1") (pintype "passive"))
      (node (ref "C237") (pin "1") (pinfunction "1_1") (pintype "passive"))
      (node (ref "C238") (pin "1") (pinfunction "1_1") (pintype "passive"))
      (node (ref "C239") (pin "1") (pinfunction "1_1") (pintype "passive"))
      (node (ref "C240") (pin "1") (pinfunction "1_1") (pintype "passive"))
      (node (ref "C241") (pin "1") (pinfunction "1_1") (pintype "passive"))
      (node (ref "C253") (pin "1") (pinfunction "1_1") (pintype "passive"))
      (node (ref "C254") (pin "1") (pinfunction "1_1") (pintype "passive"))
      (node (ref "C261") (pin "1") (pinfunction "1_1") (pintype "passive"))
      (node (ref "C262") (pin "1") (pinfunction "1_1") (pintype "passive"))
      (node (ref "C263") (pin "2") (pinfunction "2_2") (pintype "passive"))
      (node (ref "C264") (pin "1") (pinfunction "1_1") (pintype "passive"))
      (node (ref "C265") (pin "1") (pinfunction "1_1") (pintype "passive"))
      (node (ref "C266") (pin "1") (pinfunction "1_1") (pintype "passive"))
      (node (ref "C269") (pin "1") (pinfunction "1_1") (pintype "passive"))
      (node (ref "C270") (pin "1") (pinfunction "1_1") (pintype "passive"))
      (node (ref "C271") (pin "1") (pinfunction "1_1") (pintype "passive"))
      (node (ref "C272") (pin "1") (pinfunction "1_1") (pintype "passive"))
      (node (ref "C273") (pin "1") (pinfunction "1_1") (pintype "passive"))
      (node (ref "C274") (pin "1") (pinfunction "1_1") (pintype "passive"))
      (node (ref "C275") (pin "1") (pinfunction "1_1") (pintype "passive"))
      (node (ref "C276") (pin "1") (pinfunction "1_1") (pintype "passive"))
      (node (ref "C277") (pin "1") (pinfunction "1_1") (pintype "passive"))
      (node (ref "C278") (pin "1") (pinfunction "1_1") (pintype "passive"))
      (node (ref "C279") (pin "1") (pinfunction "1_1") (pintype "passive"))
      (node (ref "C280") (pin "1") (pinfunction "1_1") (pintype "passive"))
      (node (ref "C281") (pin "1") (pinfunction "1_1") (pintype "passive"))
      (node (ref "C282") (pin "1") (pinfunction "1_1") (pintype "passive"))
      (node (ref "C283") (pin "1") (pinfunction "1_1") (pintype "passive"))
      (node (ref "C284") (pin "1") (pinfunction "1_1") (pintype "passive"))
      (node (ref "C285") (pin "1") (pinfunction "1_1") (pintype "passive"))
      (node (ref "C286") (pin "1") (pinfunction "1_1") (pintype "passive"))
      (node (ref "C287") (pin "1") (pinfunction "1_1") (pintype "passive"))
      (node (ref "C288") (pin "1") (pinfunction "1_1") (pintype "passive"))
      (node (ref "C289") (pin "1") (pinfunction "1_1") (pintype "passive"))
      (node (ref "C292") (pin "1") (pinfunction "1_1") (pintype "passive"))
      (node (ref "C98") (pin "1") (pinfunction "1_1") (pintype "passive"))
      (node (ref "D2") (pin "2") (pinfunction "A_2") (pintype "passive"))
      (node (ref "HS2") (pin "1") (pinfunction "1_1") (pintype "passive"))
      (node (ref "IC17") (pin "2") (pinfunction "S_2") (pintype "passive"))
      (node (ref "IC18") (pin "10") (pinfunction "VSS_10") (pintype "power_in"))
      (node (ref "IC9") (pin "A1") (pinfunction "GND_A1") (pintype "power_in"))
      (node (ref "IC9") (pin "A11") (pinfunction "GND_A11") (pintype "power_in"))
      (node (ref "IC9") (pin "A16") (pinfunction "GND_A16") (pintype "power_in"))
      (node (ref "IC9") (pin "A2") (pinfunction "GND_A2") (pintype "power_in"))
      (node (ref "IC9") (pin "A21") (pinfunction "GND_A21") (pintype "power_in"))
      (node (ref "IC9") (pin "A26") (pinfunction "GND_A26") (pintype "power_in"))
      (node (ref "IC9") (pin "A5") (pinfunction "GND_A5") (pintype "power_in"))
      (node (ref "IC9") (pin "A6") (pinfunction "GND_A6") (pintype "power_in"))
      (node (ref "IC9") (pin "A8") (pinfunction "GND_A8") (pintype "power_in"))
      (node (ref "IC9") (pin "AA1") (pinfunction "GND_AA1") (pintype "power_in"))
      (node (ref "IC9") (pin "AA16") (pinfunction "GND_AA16") (pintype "power_in"))
      (node (ref "IC9") (pin "AA2") (pinfunction "GND_AA2") (pintype "power_in"))
      (node (ref "IC9") (pin "AA26") (pinfunction "GND_AA26") (pintype "power_in"))
      (node (ref "IC9") (pin "AA3") (pinfunction "GND_AA3") (pintype "power_in"))
      (node (ref "IC9") (pin "AA6") (pinfunction "GND_AA6") (pintype "power_in"))
      (node (ref "IC9") (pin "AA8") (pinfunction "GND_AA8") (pintype "power_in"))
      (node (ref "IC9") (pin "AB13") (pinfunction "GND_AB13") (pintype "power_in"))
      (node (ref "IC9") (pin "AB23") (pinfunction "GND_AB23") (pintype "power_in"))
      (node (ref "IC9") (pin "AB3") (pinfunction "GND_AB3") (pintype "power_in"))
      (node (ref "IC9") (pin "AB4") (pinfunction "GND_AB4") (pintype "power_in"))
      (node (ref "IC9") (pin "AB8") (pinfunction "GND_AB8") (pintype "power_in"))
      (node (ref "IC9") (pin "AC1") (pinfunction "GND_AC1") (pintype "power_in"))
      (node (ref "IC9") (pin "AC10") (pinfunction "GND_AC10") (pintype "power_in"))
      (node (ref "IC9") (pin "AC2") (pinfunction "GND_AC2") (pintype "power_in"))
      (node (ref "IC9") (pin "AC20") (pinfunction "GND_AC20") (pintype "power_in"))
      (node (ref "IC9") (pin "AC25") (pinfunction "GND_AC25") (pintype "power_in"))
      (node (ref "IC9") (pin "AC3") (pinfunction "GND_AC3") (pintype "power_in"))
      (node (ref "IC9") (pin "AC6") (pinfunction "GND_AC6") (pintype "power_in"))
      (node (ref "IC9") (pin "AC8") (pinfunction "GND_AC8") (pintype "power_in"))
      (node (ref "IC9") (pin "AC9") (pinfunction "GND_AC9") (pintype "power_in"))
      (node (ref "IC9") (pin "AD10") (pinfunction "GND_AD10") (pintype "power_in"))
      (node (ref "IC9") (pin "AD17") (pinfunction "GND_AD17") (pintype "power_in"))
      (node (ref "IC9") (pin "AD3") (pinfunction "GND_AD3") (pintype "power_in"))
      (node (ref "IC9") (pin "AD4") (pinfunction "GND_AD4") (pintype "power_in"))
      (node (ref "IC9") (pin "AD5") (pinfunction "GND_AD5") (pintype "power_in"))
      (node (ref "IC9") (pin "AD8") (pinfunction "MGTAVTTRCAL_R_AD8") (pintype "passive"))
      (node (ref "IC9") (pin "AD9") (pinfunction "MGTRREF_R_AD9") (pintype "input"))
      (node (ref "IC9") (pin "AE1") (pinfunction "GND_AE1") (pintype "power_in"))
      (node (ref "IC9") (pin "AE10") (pinfunction "GND_AE10") (pintype "power_in"))
      (node (ref "IC9") (pin "AE14") (pinfunction "GND_AE14") (pintype "power_in"))
      (node (ref "IC9") (pin "AE19") (pinfunction "GND_AE19") (pintype "power_in"))
      (node (ref "IC9") (pin "AE2") (pinfunction "GND_AE2") (pintype "power_in"))
      (node (ref "IC9") (pin "AE24") (pinfunction "GND_AE24") (pintype "power_in"))
      (node (ref "IC9") (pin "AE5") (pinfunction "GND_AE5") (pintype "power_in"))
      (node (ref "IC9") (pin "AE6") (pinfunction "GND_AE6") (pintype "power_in"))
      (node (ref "IC9") (pin "AF10") (pinfunction "GND_AF10") (pintype "power_in"))
      (node (ref "IC9") (pin "AF11") (pinfunction "GND_AF11") (pintype "power_in"))
      (node (ref "IC9") (pin "AF16") (pinfunction "GND_AF16") (pintype "power_in"))
      (node (ref "IC9") (pin "AF21") (pinfunction "GND_AF21") (pintype "power_in"))
      (node (ref "IC9") (pin "AF26") (pinfunction "GND_AF26") (pintype "power_in"))
      (node (ref "IC9") (pin "AF3") (pinfunction "GND_AF3") (pintype "power_in"))
      (node (ref "IC9") (pin "AF4") (pinfunction "GND_AF4") (pintype "power_in"))
      (node (ref "IC9") (pin "AF5") (pinfunction "GND_AF5") (pintype "power_in"))
      (node (ref "IC9") (pin "AF8") (pinfunction "GND_AF8") (pintype "power_in"))
      (node (ref "IC9") (pin "AF9") (pinfunction "GND_AF9") (pintype "power_in"))
      (node (ref "IC9") (pin "B13") (pinfunction "GND_B13") (pintype "power_in"))
      (node (ref "IC9") (pin "B18") (pinfunction "GND_B18") (pintype "power_in"))
      (node (ref "IC9") (pin "B23") (pinfunction "GND_B23") (pintype "power_in"))
      (node (ref "IC9") (pin "B3") (pinfunction "GND_B3") (pintype "power_in"))
      (node (ref "IC9") (pin "B4") (pinfunction "GND_B4") (pintype "power_in"))
      (node (ref "IC9") (pin "B5") (pinfunction "GND_B5") (pintype "power_in"))
      (node (ref "IC9") (pin "B8") (pinfunction "GND_B8") (pintype "power_in"))
      (node (ref "IC9") (pin "C1") (pinfunction "GND_C1") (pintype "power_in"))
      (node (ref "IC9") (pin "C10") (pinfunction "GND_C10") (pintype "power_in"))
      (node (ref "IC9") (pin "C15") (pinfunction "GND_C15") (pintype "power_in"))
      (node (ref "IC9") (pin "C2") (pinfunction "GND_C2") (pintype "power_in"))
      (node (ref "IC9") (pin "C25") (pinfunction "GND_C25") (pintype "power_in"))
      (node (ref "IC9") (pin "C5") (pinfunction "GND_C5") (pintype "power_in"))
      (node (ref "IC9") (pin "C6") (pinfunction "GND_C6") (pintype "power_in"))
      (node (ref "IC9") (pin "C8") (pinfunction "GND_C8") (pintype "power_in"))
      (node (ref "IC9") (pin "D12") (pinfunction "GND_D12") (pintype "power_in"))
      (node (ref "IC9") (pin "D22") (pinfunction "GND_D22") (pintype "power_in"))
      (node (ref "IC9") (pin "D3") (pinfunction "GND_D3") (pintype "power_in"))
      (node (ref "IC9") (pin "D4") (pinfunction "GND_D4") (pintype "power_in"))
      (node (ref "IC9") (pin "D5") (pinfunction "GND_D5") (pintype "power_in"))
      (node (ref "IC9") (pin "D8") (pinfunction "GND_D8") (pintype "power_in"))
      (node (ref "IC9") (pin "E1") (pinfunction "GND_E1") (pintype "power_in"))
      (node (ref "IC9") (pin "E19") (pinfunction "GND_E19") (pintype "power_in"))
      (node (ref "IC9") (pin "E2") (pinfunction "GND_E2") (pintype "power_in"))
      (node (ref "IC9") (pin "E3") (pinfunction "GND_E3") (pintype "power_in"))
      (node (ref "IC9") (pin "E6") (pinfunction "GND_E6") (pintype "power_in"))
      (node (ref "IC9") (pin "E8") (pinfunction "GND_E8") (pintype "power_in"))
      (node (ref "IC9") (pin "F11") (pinfunction "GND_F11") (pintype "power_in"))
      (node (ref "IC9") (pin "F16") (pinfunction "GND_F16") (pintype "power_in"))
      (node (ref "IC9") (pin "F21") (pinfunction "GND_F21") (pintype "power_in"))
      (node (ref "IC9") (pin "F26") (pinfunction "GND_F26") (pintype "power_in"))
      (node (ref "IC9") (pin "F3") (pinfunction "GND_F3") (pintype "power_in"))
      (node (ref "IC9") (pin "F4") (pinfunction "GND_F4") (pintype "power_in"))
      (node (ref "IC9") (pin "F8") (pinfunction "GND_F8") (pintype "power_in"))
      (node (ref "IC9") (pin "G1") (pinfunction "GND_G1") (pintype "power_in"))
      (node (ref "IC9") (pin "G13") (pinfunction "GND_G13") (pintype "power_in"))
      (node (ref "IC9") (pin "G2") (pinfunction "GND_G2") (pintype "power_in"))
      (node (ref "IC9") (pin "G23") (pinfunction "GND_G23") (pintype "power_in"))
      (node (ref "IC9") (pin "G3") (pinfunction "GND_G3") (pintype "power_in"))
      (node (ref "IC9") (pin "G6") (pinfunction "GND_G6") (pintype "power_in"))
      (node (ref "IC9") (pin "G8") (pinfunction "GND_G8") (pintype "power_in"))
      (node (ref "IC9") (pin "H20") (pinfunction "GND_H20") (pintype "power_in"))
      (node (ref "IC9") (pin "H3") (pinfunction "GND_H3") (pintype "power_in"))
      (node (ref "IC9") (pin "H4") (pinfunction "GND_H4") (pintype "power_in"))
      (node (ref "IC9") (pin "H8") (pinfunction "GND_H8") (pintype "power_in"))
      (node (ref "IC9") (pin "J1") (pinfunction "GND_J1") (pintype "power_in"))
      (node (ref "IC9") (pin "J17") (pinfunction "GND_J17") (pintype "power_in"))
      (node (ref "IC9") (pin "J2") (pinfunction "GND_J2") (pintype "power_in"))
      (node (ref "IC9") (pin "J3") (pinfunction "GND_J3") (pintype "power_in"))
      (node (ref "IC9") (pin "J6") (pinfunction "GND_J6") (pintype "power_in"))
      (node (ref "IC9") (pin "J8") (pinfunction "GND_J8") (pintype "power_in"))
      (node (ref "IC9") (pin "K12") (pinfunction "GND_K12") (pintype "power_in"))
      (node (ref "IC9") (pin "K14") (pinfunction "GND_K14") (pintype "power_in"))
      (node (ref "IC9") (pin "K16") (pinfunction "GND_K16") (pintype "power_in"))
      (node (ref "IC9") (pin "K19") (pinfunction "GND_K19") (pintype "power_in"))
      (node (ref "IC9") (pin "K24") (pinfunction "GND_K24") (pintype "power_in"))
      (node (ref "IC9") (pin "K3") (pinfunction "GND_K3") (pintype "power_in"))
      (node (ref "IC9") (pin "K4") (pinfunction "GND_K4") (pintype "power_in"))
      (node (ref "IC9") (pin "K8") (pinfunction "GND_K8") (pintype "power_in"))
      (node (ref "IC9") (pin "L1") (pinfunction "GND_L1") (pintype "power_in"))
      (node (ref "IC9") (pin "L11") (pinfunction "GND_L11") (pintype "power_in"))
      (node (ref "IC9") (pin "L13") (pinfunction "GND_L13") (pintype "power_in"))
      (node (ref "IC9") (pin "L15") (pinfunction "GND_L15") (pintype "power_in"))
      (node (ref "IC9") (pin "L17") (pinfunction "GND_L17") (pintype "power_in"))
      (node (ref "IC9") (pin "L2") (pinfunction "GND_L2") (pintype "power_in"))
      (node (ref "IC9") (pin "L21") (pinfunction "GND_L21") (pintype "power_in"))
      (node (ref "IC9") (pin "L26") (pinfunction "GND_L26") (pintype "power_in"))
      (node (ref "IC9") (pin "L3") (pinfunction "GND_L3") (pintype "power_in"))
      (node (ref "IC9") (pin "L6") (pinfunction "GND_L6") (pintype "power_in"))
      (node (ref "IC9") (pin "L8") (pinfunction "GND_L8") (pintype "power_in"))
      (node (ref "IC9") (pin "M10") (pinfunction "GND_M10") (pintype "power_in"))
      (node (ref "IC9") (pin "M12") (pinfunction "GND_M12") (pintype "power_in"))
      (node (ref "IC9") (pin "M14") (pinfunction "GND_M14") (pintype "power_in"))
      (node (ref "IC9") (pin "M16") (pinfunction "GND_M16") (pintype "power_in"))
      (node (ref "IC9") (pin "M23") (pinfunction "GND_M23") (pintype "power_in"))
      (node (ref "IC9") (pin "M3") (pinfunction "GND_M3") (pintype "power_in"))
      (node (ref "IC9") (pin "M4") (pinfunction "GND_M4") (pintype "power_in"))
      (node (ref "IC9") (pin "M8") (pinfunction "GND_M8") (pintype "power_in"))
      (node (ref "IC9") (pin "N1") (pinfunction "GND_N1") (pintype "power_in"))
      (node (ref "IC9") (pin "N11") (pinfunction "GND_N11") (pintype "power_in"))
      (node (ref "IC9") (pin "N15") (pinfunction "GND_N15") (pintype "power_in"))
      (node (ref "IC9") (pin "N17") (pinfunction "GND_N17") (pintype "power_in"))
      (node (ref "IC9") (pin "N2") (pinfunction "GND_N2") (pintype "power_in"))
      (node (ref "IC9") (pin "N20") (pinfunction "GND_N20") (pintype "power_in"))
      (node (ref "IC9") (pin "N25") (pinfunction "GND_N25") (pintype "power_in"))
      (node (ref "IC9") (pin "N3") (pinfunction "GND_N3") (pintype "power_in"))
      (node (ref "IC9") (pin "N6") (pinfunction "GND_N6") (pintype "power_in"))
      (node (ref "IC9") (pin "N8") (pinfunction "GND_N8") (pintype "power_in"))
      (node (ref "IC9") (pin "P10") (pinfunction "GND_P10") (pintype "power_in"))
      (node (ref "IC9") (pin "P12") (pinfunction "GND_P12") (pintype "power_in"))
      (node (ref "IC9") (pin "P16") (pinfunction "GND_P16") (pintype "power_in"))
      (node (ref "IC9") (pin "P3") (pinfunction "GND_P3") (pintype "power_in"))
      (node (ref "IC9") (pin "P4") (pinfunction "GND_P4") (pintype "power_in"))
      (node (ref "IC9") (pin "P8") (pinfunction "GND_P8") (pintype "power_in"))
      (node (ref "IC9") (pin "R1") (pinfunction "GND_R1") (pintype "power_in"))
      (node (ref "IC9") (pin "R11") (pinfunction "GND_R11") (pintype "power_in"))
      (node (ref "IC9") (pin "R15") (pinfunction "GND_R15") (pintype "power_in"))
      (node (ref "IC9") (pin "R17") (pinfunction "GND_R17") (pintype "power_in"))
      (node (ref "IC9") (pin "R19") (pinfunction "GND_R19") (pintype "power_in"))
      (node (ref "IC9") (pin "R2") (pinfunction "GND_R2") (pintype "power_in"))
      (node (ref "IC9") (pin "R24") (pinfunction "GND_R24") (pintype "power_in"))
      (node (ref "IC9") (pin "R3") (pinfunction "GND_R3") (pintype "power_in"))
      (node (ref "IC9") (pin "R6") (pinfunction "GND_R6") (pintype "power_in"))
      (node (ref "IC9") (pin "R8") (pinfunction "GND_R8") (pintype "power_in"))
      (node (ref "IC9") (pin "T10") (pinfunction "GND_T10") (pintype "power_in"))
      (node (ref "IC9") (pin "T12") (pinfunction "GND_T12") (pintype "power_in"))
      (node (ref "IC9") (pin "T13") (pinfunction "DXN_T13") (pintype "input"))
      (node (ref "IC9") (pin "T14") (pinfunction "DXP_T14") (pintype "input"))
      (node (ref "IC9") (pin "T16") (pinfunction "GND_T16") (pintype "power_in"))
      (node (ref "IC9") (pin "T21") (pinfunction "GND_T21") (pintype "power_in"))
      (node (ref "IC9") (pin "T26") (pinfunction "GND_T26") (pintype "power_in"))
      (node (ref "IC9") (pin "T3") (pinfunction "GND_T3") (pintype "power_in"))
      (node (ref "IC9") (pin "T4") (pinfunction "GND_T4") (pintype "power_in"))
      (node (ref "IC9") (pin "T8") (pinfunction "GND_T8") (pintype "power_in"))
      (node (ref "IC9") (pin "U1") (pinfunction "GND_U1") (pintype "power_in"))
      (node (ref "IC9") (pin "U11") (pinfunction "GND_U11") (pintype "power_in"))
      (node (ref "IC9") (pin "U13") (pinfunction "GND_U13") (pintype "power_in"))
      (node (ref "IC9") (pin "U15") (pinfunction "GND_U15") (pintype "power_in"))
      (node (ref "IC9") (pin "U17") (pinfunction "GND_U17") (pintype "power_in"))
      (node (ref "IC9") (pin "U18") (pinfunction "GND_U18") (pintype "power_in"))
      (node (ref "IC9") (pin "U2") (pinfunction "GND_U2") (pintype "power_in"))
      (node (ref "IC9") (pin "U3") (pinfunction "GND_U3") (pintype "power_in"))
      (node (ref "IC9") (pin "U6") (pinfunction "GND_U6") (pintype "power_in"))
      (node (ref "IC9") (pin "U8") (pinfunction "GND_U8") (pintype "power_in"))
      (node (ref "IC9") (pin "V10") (pinfunction "GND_V10") (pintype "power_in"))
      (node (ref "IC9") (pin "V12") (pinfunction "GND_V12") (pintype "power_in"))
      (node (ref "IC9") (pin "V14") (pinfunction "GND_V14") (pintype "power_in"))
      (node (ref "IC9") (pin "V16") (pinfunction "GND_V16") (pintype "power_in"))
      (node (ref "IC9") (pin "V20") (pinfunction "GND_V20") (pintype "power_in"))
      (node (ref "IC9") (pin "V25") (pinfunction "GND_V25") (pintype "power_in"))
      (node (ref "IC9") (pin "V3") (pinfunction "GND_V3") (pintype "power_in"))
      (node (ref "IC9") (pin "V4") (pinfunction "GND_V4") (pintype "power_in"))
      (node (ref "IC9") (pin "V8") (pinfunction "GND_V8") (pintype "power_in"))
      (node (ref "IC9") (pin "W1") (pinfunction "GND_W1") (pintype "power_in"))
      (node (ref "IC9") (pin "W17") (pinfunction "GND_W17") (pintype "power_in"))
      (node (ref "IC9") (pin "W2") (pinfunction "GND_W2") (pintype "power_in"))
      (node (ref "IC9") (pin "W22") (pinfunction "GND_W22") (pintype "power_in"))
      (node (ref "IC9") (pin "W3") (pinfunction "GND_W3") (pintype "power_in"))
      (node (ref "IC9") (pin "W6") (pinfunction "GND_W6") (pintype "power_in"))
      (node (ref "IC9") (pin "W8") (pinfunction "GND_W8") (pintype "power_in"))
      (node (ref "IC9") (pin "Y19") (pinfunction "GND_Y19") (pintype "power_in"))
      (node (ref "IC9") (pin "Y3") (pinfunction "GND_Y3") (pintype "power_in"))
      (node (ref "IC9") (pin "Y4") (pinfunction "GND_Y4") (pintype "power_in"))
      (node (ref "IC9") (pin "Y8") (pinfunction "GND_Y8") (pintype "power_in"))
      (node (ref "IC9") (pin "Y9") (pinfunction "VBATT_Y9") (pintype "power_in"))
      (node (ref "J3") (pin "1") (pinfunction "1_1") (pintype "bidirectional"))
      (node (ref "J3") (pin "11") (pinfunction "11_11") (pintype "bidirectional"))
      (node (ref "J3") (pin "13") (pinfunction "13_13") (pintype "bidirectional"))
      (node (ref "J3") (pin "3") (pinfunction "3_3") (pintype "bidirectional"))
      (node (ref "J3") (pin "5") (pinfunction "5_5") (pintype "bidirectional"))
      (node (ref "J3") (pin "7") (pinfunction "7_7") (pintype "bidirectional"))
      (node (ref "J3") (pin "9") (pinfunction "9_9") (pintype "bidirectional"))
      (node (ref "L16") (pin "2") (pinfunction "2_2") (pintype "passive"))
      (node (ref "R179") (pin "1") (pinfunction "1_1") (pintype "passive"))
      (node (ref "R180") (pin "1") (pinfunction "1_1") (pintype "passive"))
      (node (ref "R181") (pin "1") (pinfunction "1_1") (pintype "passive"))
      (node (ref "R182") (pin "1") (pinfunction "1_1") (pintype "passive"))
      (node (ref "R183") (pin "1") (pinfunction "1_1") (pintype "passive"))
      (node (ref "SW2") (pin "1") (pinfunction "1_1") (pintype "bidirectional"))
      (node (ref "SW2") (pin "2") (pinfunction "2_2") (pintype "bidirectional"))
      (node (ref "SW2") (pin "3") (pinfunction "3_3") (pintype "bidirectional"))
      (node (ref "SW2") (pin "4") (pinfunction "4_4") (pintype "bidirectional"))
    )
    (net (code "26") (name "GNDADC2") (class "Default")
      (node (ref "C290") (pin "1") (pinfunction "1_1") (pintype "passive"))
      (node (ref "C291") (pin "1") (pinfunction "1_1") (pintype "passive"))
      (node (ref "IC9") (pin "N13") (pinfunction "GNDADC_N13") (pintype "power_in"))
      (node (ref "IC9") (pin "P13") (pinfunction "VREFN_P13") (pintype "input"))
      (node (ref "IC9") (pin "P14") (pinfunction "VP_P14") (pintype "input"))
      (node (ref "IC9") (pin "R13") (pinfunction "VN_R13") (pintype "input"))
      (node (ref "IC9") (pin "R14") (pinfunction "VREFP_R14") (pintype "input"))
      (node (ref "L16") (pin "1") (pinfunction "1_1") (pintype "passive"))
    )
    (net (code "27") (name "Net-(IC9K-VCCADC)") (class "Default")
      (node (ref "C290") (pin "2") (pinfunction "2_2") (pintype "passive"))
      (node (ref "C291") (pin "2") (pinfunction "2_2") (pintype "passive"))
      (node (ref "IC9") (pin "N14") (pinfunction "VCCADC_N14") (pintype "power_in"))
      (node (ref "L11") (pin "1") (pinfunction "1_1") (pintype "passive"))
    )
    (net (code "28") (name "Net-(IC9K-VREF_64)") (class "Default")
      (node (ref "IC9") (pin "W18") (pinfunction "VREF_64_W18") (pintype "power_in"))
      (node (ref "TP5") (pin "1") (pinfunction "1_1") (pintype "bidirectional"))
    )
    (net (code "29") (name "Net-(IC9K-VREF_65)") (class "Default")
      (node (ref "IC9") (pin "V18") (pinfunction "VREF_65_V18") (pintype "power_in"))
      (node (ref "TP6") (pin "1") (pinfunction "1_1") (pintype "bidirectional"))
    )
    (net (code "30") (name "Net-(IC9K-VREF_66)") (class "Default")
      (node (ref "IC9") (pin "J18") (pinfunction "VREF_66_J18") (pintype "power_in"))
      (node (ref "TP7") (pin "1") (pinfunction "1_1") (pintype "bidirectional"))
    )
    (net (code "31") (name "Net-(IC18-~{RESET})") (class "Default")
      (node (ref "IC18") (pin "3") (pinfunction "~{RESET}_3") (pintype "input"))
      (node (ref "R196") (pin "2") (pinfunction "2_2") (pintype "passive"))
    )
    (net (code "32") (name "Net-(J3-Pad14)") (class "Default")
      (node (ref "J3") (pin "14") (pinfunction "14_14") (pintype "bidirectional"))
      (node (ref "R184") (pin "1") (pinfunction "1_1") (pintype "passive"))
    )
    (net (code "33") (name "P0V85") (class "Default")
      (node (ref "C101") (pin "2") (pinfunction "2_2") (pintype "passive"))
      (node (ref "C102") (pin "2") (pinfunction "2_2") (pintype "passive"))
      (node (ref "C103") (pin "2") (pinfunction "2_2") (pintype "passive"))
      (node (ref "C104") (pin "2") (pinfunction "2_2") (pintype "passive"))
      (node (ref "C237") (pin "2") (pinfunction "2_2") (pintype "passive"))
      (node (ref "C238") (pin "2") (pinfunction "2_2") (pintype "passive"))
      (node (ref "C239") (pin "2") (pinfunction "2_2") (pintype "passive"))
      (node (ref "C240") (pin "2") (pinfunction "2_2") (pintype "passive"))
      (node (ref "C241") (pin "2") (pinfunction "2_2") (pintype "passive"))
      (node (ref "C253") (pin "2") (pinfunction "2_2") (pintype "passive"))
      (node (ref "C254") (pin "2") (pinfunction "2_2") (pintype "passive"))
      (node (ref "C261") (pin "2") (pinfunction "2_2") (pintype "passive"))
      (node (ref "C262") (pin "2") (pinfunction "2_2") (pintype "passive"))
      (node (ref "C263") (pin "1") (pinfunction "1_1") (pintype "passive"))
      (node (ref "C98") (pin "2") (pinfunction "2_2") (pintype "passive"))
      (node (ref "IC9") (pin "K11") (pinfunction "VCCINT_K11") (pintype "power_in"))
      (node (ref "IC9") (pin "K13") (pinfunction "VCCINT_K13") (pintype "power_in"))
      (node (ref "IC9") (pin "K15") (pinfunction "VCCINT_K15") (pintype "power_in"))
      (node (ref "IC9") (pin "K17") (pinfunction "VCCINT_K17") (pintype "power_in"))
      (node (ref "IC9") (pin "L10") (pinfunction "VCCINT_L10") (pintype "power_in"))
      (node (ref "IC9") (pin "L12") (pinfunction "VCCINT_L12") (pintype "power_in"))
      (node (ref "IC9") (pin "L14") (pinfunction "VCCINT_L14") (pintype "power_in"))
      (node (ref "IC9") (pin "L16") (pinfunction "VCCINT_L16") (pintype "power_in"))
      (node (ref "IC9") (pin "L9") (pinfunction "VCCINT_IO_L9") (pintype "power_in"))
      (node (ref "IC9") (pin "M11") (pinfunction "VCCINT_M11") (pintype "power_in"))
      (node (ref "IC9") (pin "M13") (pinfunction "VCCINT_M13") (pintype "power_in"))
      (node (ref "IC9") (pin "M15") (pinfunction "VCCINT_M15") (pintype "power_in"))
      (node (ref "IC9") (pin "M17") (pinfunction "VCCINT_M17") (pintype "power_in"))
      (node (ref "IC9") (pin "M9") (pinfunction "VCCINT_IO_M9") (pintype "power_in"))
      (node (ref "IC9") (pin "N10") (pinfunction "VCCINT_N10") (pintype "power_in"))
      (node (ref "IC9") (pin "N12") (pinfunction "VCCINT_N12") (pintype "power_in"))
      (node (ref "IC9") (pin "N16") (pinfunction "VCCINT_N16") (pintype "power_in"))
      (node (ref "IC9") (pin "N9") (pinfunction "VCCINT_IO_N9") (pintype "power_in"))
      (node (ref "IC9") (pin "P11") (pinfunction "VCCINT_P11") (pintype "power_in"))
      (node (ref "IC9") (pin "P15") (pinfunction "VCCINT_P15") (pintype "power_in"))
      (node (ref "IC9") (pin "P17") (pinfunction "VCCINT_P17") (pintype "power_in"))
      (node (ref "IC9") (pin "P9") (pinfunction "VCCINT_IO_P9") (pintype "power_in"))
      (node (ref "IC9") (pin "R10") (pinfunction "VCCINT_R10") (pintype "power_in"))
      (node (ref "IC9") (pin "R12") (pinfunction "VCCINT_R12") (pintype "power_in"))
      (node (ref "IC9") (pin "R16") (pinfunction "VCCINT_R16") (pintype "power_in"))
      (node (ref "IC9") (pin "R9") (pinfunction "VCCBRAM_R9") (pintype "power_in"))
      (node (ref "IC9") (pin "T11") (pinfunction "VCCINT_T11") (pintype "power_in"))
      (node (ref "IC9") (pin "T15") (pinfunction "VCCINT_T15") (pintype "power_in"))
      (node (ref "IC9") (pin "T17") (pinfunction "VCCINT_T17") (pintype "power_in"))
      (node (ref "IC9") (pin "T9") (pinfunction "VCCBRAM_T9") (pintype "power_in"))
      (node (ref "IC9") (pin "U10") (pinfunction "VCCINT_U10") (pintype "power_in"))
      (node (ref "IC9") (pin "U12") (pinfunction "VCCINT_U12") (pintype "power_in"))
      (node (ref "IC9") (pin "U14") (pinfunction "VCCINT_U14") (pintype "power_in"))
      (node (ref "IC9") (pin "U16") (pinfunction "VCCINT_U16") (pintype "power_in"))
      (node (ref "IC9") (pin "U9") (pinfunction "VCCBRAM_U9") (pintype "power_in"))
      (node (ref "IC9") (pin "V11") (pinfunction "VCCINT_V11") (pintype "power_in"))
      (node (ref "IC9") (pin "V13") (pinfunction "VCCINT_V13") (pintype "power_in"))
      (node (ref "IC9") (pin "V15") (pinfunction "VCCINT_V15") (pintype "power_in"))
      (node (ref "IC9") (pin "V17") (pinfunction "VCCINT_V17") (pintype "power_in"))
      (node (ref "IC9") (pin "V9") (pinfunction "VCCBRAM_V9") (pintype "power_in"))
      (node (ref "R174") (pin "2") (pinfunction "2_2") (pintype "passive"))
    )
    (net (code "34") (name "P1V8") (class "Default")
      (node (ref "C264") (pin "2") (pinfunction "2_2") (pintype "passive"))
      (node (ref "C265") (pin "2") (pinfunction "2_2") (pintype "passive"))
      (node (ref "C266") (pin "2") (pinfunction "2_2") (pintype "passive"))
      (node (ref "C269") (pin "2") (pinfunction "2_2") (pintype "passive"))
      (node (ref "C270") (pin "2") (pinfunction "2_2") (pintype "passive"))
      (node (ref "C271") (pin "2") (pinfunction "2_2") (pintype "passive"))
      (node (ref "C272") (pin "2") (pinfunction "2_2") (pintype "passive"))
      (node (ref "C273") (pin "2") (pinfunction "2_2") (pintype "passive"))
      (node (ref "C274") (pin "2") (pinfunction "2_2") (pintype "passive"))
      (node (ref "C275") (pin "2") (pinfunction "2_2") (pintype "passive"))
      (node (ref "C276") (pin "2") (pinfunction "2_2") (pintype "passive"))
      (node (ref "C277") (pin "2") (pinfunction "2_2") (pintype "passive"))
      (node (ref "C278") (pin "2") (pinfunction "2_2") (pintype "passive"))
      (node (ref "C279") (pin "2") (pinfunction "2_2") (pintype "passive"))
      (node (ref "C280") (pin "2") (pinfunction "2_2") (pintype "passive"))
      (node (ref "IC9") (pin "AC15") (pinfunction "VCCO_84_AC15") (pintype "power_in"))
      (node (ref "IC9") (pin "E14") (pinfunction "VCCO_86_E14") (pintype "power_in"))
      (node (ref "IC9") (pin "E9") (pinfunction "VCCO_85_E9") (pintype "power_in"))
      (node (ref "IC9") (pin "H10") (pinfunction "VCCO_85_H10") (pintype "power_in"))
      (node (ref "IC9") (pin "H15") (pinfunction "VCCO_86_H15") (pintype "power_in"))
      (node (ref "IC9") (pin "M18") (pinfunction "VCCAUX_M18") (pintype "power_in"))
      (node (ref "IC9") (pin "N18") (pinfunction "VCCAUX_N18") (pintype "power_in"))
      (node (ref "IC9") (pin "P18") (pinfunction "VCCAUX_IO_P18") (pintype "power_in"))
      (node (ref "IC9") (pin "R18") (pinfunction "VCCAUX_IO_R18") (pintype "power_in"))
      (node (ref "IC9") (pin "T18") (pinfunction "VCCAUX_IO_T18") (pintype "power_in"))
      (node (ref "IC9") (pin "Y14") (pinfunction "VCCO_84_Y14") (pintype "power_in"))
      (node (ref "L11") (pin "2") (pinfunction "2_2") (pintype "passive"))
    )
    (net (code "35") (name "P3V3") (class "Default")
      (node (ref "C281") (pin "2") (pinfunction "2_2") (pintype "passive"))
      (node (ref "C282") (pin "2") (pinfunction "2_2") (pintype "passive"))
      (node (ref "C283") (pin "2") (pinfunction "2_2") (pintype "passive"))
      (node (ref "C284") (pin "2") (pinfunction "2_2") (pintype "passive"))
      (node (ref "C285") (pin "2") (pinfunction "2_2") (pintype "passive"))
      (node (ref "C286") (pin "2") (pinfunction "2_2") (pintype "passive"))
      (node (ref "C287") (pin "2") (pinfunction "2_2") (pintype "passive"))
      (node (ref "C288") (pin "2") (pinfunction "2_2") (pintype "passive"))
      (node (ref "C289") (pin "2") (pinfunction "2_2") (pintype "passive"))
      (node (ref "C292") (pin "2") (pinfunction "2_2") (pintype "passive"))
      (node (ref "IC18") (pin "2") (pinfunction "VCC_2") (pintype "power_in"))
      (node (ref "IC9") (pin "AA11") (pinfunction "VCCO_0_AA11") (pintype "power_in"))
      (node (ref "IC9") (pin "AA21") (pinfunction "VCCO_64_AA21") (pintype "power_in"))
      (node (ref "IC9") (pin "AB18") (pinfunction "VCCO_64_AB18") (pintype "power_in"))
      (node (ref "IC9") (pin "AD12") (pinfunction "VCCO_0_AD12") (pintype "power_in"))
      (node (ref "IC9") (pin "AD22") (pinfunction "VCCO_64_AD22") (pintype "power_in"))
      (node (ref "IC9") (pin "E24") (pinfunction "VCCO_66_E24") (pintype "power_in"))
      (node (ref "IC9") (pin "H25") (pinfunction "VCCO_66_H25") (pintype "power_in"))
      (node (ref "IC9") (pin "J22") (pinfunction "VCCO_66_J22") (pintype "power_in"))
      (node (ref "IC9") (pin "P22") (pinfunction "VCCO_65_P22") (pintype "power_in"))
      (node (ref "IC9") (pin "U23") (pinfunction "VCCO_65_U23") (pintype "power_in"))
      (node (ref "IC9") (pin "Y24") (pinfunction "VCCO_65_Y24") (pintype "power_in"))
      (node (ref "J3") (pin "2") (pinfunction "2_2") (pintype "bidirectional"))
      (node (ref "R170") (pin "2") (pinfunction "2_2") (pintype "passive"))
      (node (ref "R171") (pin "2") (pinfunction "2_2") (pintype "passive"))
      (node (ref "R172") (pin "2") (pinfunction "2_2") (pintype "passive"))
      (node (ref "R173") (pin "2") (pinfunction "2_2") (pintype "passive"))
      (node (ref "R175") (pin "2") (pinfunction "2_2") (pintype "passive"))
      (node (ref "R176") (pin "2") (pinfunction "2_2") (pintype "passive"))
      (node (ref "R177") (pin "2") (pinfunction "2_2") (pintype "passive"))
      (node (ref "R178") (pin "2") (pinfunction "2_2") (pintype "passive"))
      (node (ref "R184") (pin "2") (pinfunction "2_2") (pintype "passive"))
      (node (ref "R185") (pin "2") (pinfunction "2_2") (pintype "passive"))
      (node (ref "R186") (pin "2") (pinfunction "2_2") (pintype "passive"))
      (node (ref "R187") (pin "2") (pinfunction "2_2") (pintype "passive"))
      (node (ref "R188") (pin "2") (pinfunction "2_2") (pintype "passive"))
      (node (ref "R189") (pin "2") (pinfunction "2_2") (pintype "passive"))
      (node (ref "R190") (pin "2") (pinfunction "2_2") (pintype "passive"))
      (node (ref "R191") (pin "2") (pinfunction "2_2") (pintype "passive"))
      (node (ref "R196") (pin "1") (pinfunction "1_1") (pintype "passive"))
    )
    (net (code "36") (name "unconnected-(D2A-C-Pad1)") (class "Default")
      (node (ref "D2") (pin "1") (pinfunction "C_1") (pintype "passive+no_connect"))
    )
    (net (code "37") (name "unconnected-(IC9H-MGTHRXN0_224-PadAF1)") (class "Default")
      (node (ref "IC9") (pin "AF1") (pinfunction "MGTHRXN0_224_AF1") (pintype "input+no_connect"))
    )
    (net (code "38") (name "unconnected-(IC9H-MGTHRXN0_225-PadY1)") (class "Default")
      (node (ref "IC9") (pin "Y1") (pinfunction "MGTHRXN0_225_Y1") (pintype "input+no_connect"))
    )
    (net (code "39") (name "unconnected-(IC9H-MGTHRXN0_226-PadM1)") (class "Default")
      (node (ref "IC9") (pin "M1") (pinfunction "MGTHRXN0_226_M1") (pintype "input+no_connect"))
    )
    (net (code "40") (name "unconnected-(IC9H-MGTHRXN1_224-PadAE3)") (class "Default")
      (node (ref "IC9") (pin "AE3") (pinfunction "MGTHRXN1_224_AE3") (pintype "input+no_connect"))
    )
    (net (code "41") (name "unconnected-(IC9H-MGTHRXN1_225-PadV1)") (class "Default")
      (node (ref "IC9") (pin "V1") (pinfunction "MGTHRXN1_225_V1") (pintype "input+no_connect"))
    )
    (net (code "42") (name "unconnected-(IC9H-MGTHRXN1_226-PadK1)") (class "Default")
      (node (ref "IC9") (pin "K1") (pinfunction "MGTHRXN1_226_K1") (pintype "input+no_connect"))
    )
    (net (code "43") (name "unconnected-(IC9H-MGTHRXN2_224-PadAD1)") (class "Default")
      (node (ref "IC9") (pin "AD1") (pinfunction "MGTHRXN2_224_AD1") (pintype "input+no_connect"))
    )
    (net (code "44") (name "unconnected-(IC9H-MGTHRXN2_225-PadT1)") (class "Default")
      (node (ref "IC9") (pin "T1") (pinfunction "MGTHRXN2_225_T1") (pintype "input+no_connect"))
    )
    (net (code "45") (name "unconnected-(IC9H-MGTHRXN2_226-PadH1)") (class "Default")
      (node (ref "IC9") (pin "H1") (pinfunction "MGTHRXN2_226_H1") (pintype "input+no_connect"))
    )
    (net (code "46") (name "unconnected-(IC9H-MGTHRXN3_224-PadAB1)") (class "Default")
      (node (ref "IC9") (pin "AB1") (pinfunction "MGTHRXN3_224_AB1") (pintype "input+no_connect"))
    )
    (net (code "47") (name "unconnected-(IC9H-MGTHRXN3_225-PadP1)") (class "Default")
      (node (ref "IC9") (pin "P1") (pinfunction "MGTHRXN3_225_P1") (pintype "input+no_connect"))
    )
    (net (code "48") (name "unconnected-(IC9H-MGTHRXN3_226-PadF1)") (class "Default")
      (node (ref "IC9") (pin "F1") (pinfunction "MGTHRXN3_226_F1") (pintype "input+no_connect"))
    )
    (net (code "49") (name "unconnected-(IC9H-MGTHRXP0_224-PadAF2)") (class "Default")
      (node (ref "IC9") (pin "AF2") (pinfunction "MGTHRXP0_224_AF2") (pintype "input+no_connect"))
    )
    (net (code "50") (name "unconnected-(IC9H-MGTHRXP0_225-PadY2)") (class "Default")
      (node (ref "IC9") (pin "Y2") (pinfunction "MGTHRXP0_225_Y2") (pintype "input+no_connect"))
    )
    (net (code "51") (name "unconnected-(IC9H-MGTHRXP0_226-PadM2)") (class "Default")
      (node (ref "IC9") (pin "M2") (pinfunction "MGTHRXP0_226_M2") (pintype "input+no_connect"))
    )
    (net (code "52") (name "unconnected-(IC9H-MGTHRXP1_224-PadAE4)") (class "Default")
      (node (ref "IC9") (pin "AE4") (pinfunction "MGTHRXP1_224_AE4") (pintype "input+no_connect"))
    )
    (net (code "53") (name "unconnected-(IC9H-MGTHRXP1_225-PadV2)") (class "Default")
      (node (ref "IC9") (pin "V2") (pinfunction "MGTHRXP1_225_V2") (pintype "input+no_connect"))
    )
    (net (code "54") (name "unconnected-(IC9H-MGTHRXP1_226-PadK2)") (class "Default")
      (node (ref "IC9") (pin "K2") (pinfunction "MGTHRXP1_226_K2") (pintype "input+no_connect"))
    )
    (net (code "55") (name "unconnected-(IC9H-MGTHRXP2_224-PadAD2)") (class "Default")
      (node (ref "IC9") (pin "AD2") (pinfunction "MGTHRXP2_224_AD2") (pintype "input+no_connect"))
    )
    (net (code "56") (name "unconnected-(IC9H-MGTHRXP2_225-PadT2)") (class "Default")
      (node (ref "IC9") (pin "T2") (pinfunction "MGTHRXP2_225_T2") (pintype "input+no_connect"))
    )
    (net (code "57") (name "unconnected-(IC9H-MGTHRXP2_226-PadH2)") (class "Default")
      (node (ref "IC9") (pin "H2") (pinfunction "MGTHRXP2_226_H2") (pintype "input+no_connect"))
    )
    (net (code "58") (name "unconnected-(IC9H-MGTHRXP3_224-PadAB2)") (class "Default")
      (node (ref "IC9") (pin "AB2") (pinfunction "MGTHRXP3_224_AB2") (pintype "input+no_connect"))
    )
    (net (code "59") (name "unconnected-(IC9H-MGTHRXP3_225-PadP2)") (class "Default")
      (node (ref "IC9") (pin "P2") (pinfunction "MGTHRXP3_225_P2") (pintype "input+no_connect"))
    )
    (net (code "60") (name "unconnected-(IC9H-MGTHRXP3_226-PadF2)") (class "Default")
      (node (ref "IC9") (pin "F2") (pinfunction "MGTHRXP3_226_F2") (pintype "input+no_connect"))
    )
    (net (code "61") (name "unconnected-(IC9H-MGTHTXN0_224-PadAF6)") (class "Default")
      (node (ref "IC9") (pin "AF6") (pinfunction "MGTHTXN0_224_AF6") (pintype "output"))
    )
    (net (code "62") (name "unconnected-(IC9H-MGTHTXN0_225-PadAA4)") (class "Default")
      (node (ref "IC9") (pin "AA4") (pinfunction "MGTHTXN0_225_AA4") (pintype "output"))
    )
    (net (code "63") (name "unconnected-(IC9H-MGTHTXN0_226-PadN4)") (class "Default")
      (node (ref "IC9") (pin "N4") (pinfunction "MGTHTXN0_226_N4") (pintype "output"))
    )
    (net (code "64") (name "unconnected-(IC9H-MGTHTXN1_224-PadAE8)") (class "Default")
      (node (ref "IC9") (pin "AE8") (pinfunction "MGTHTXN1_224_AE8") (pintype "output"))
    )
    (net (code "65") (name "unconnected-(IC9H-MGTHTXN1_225-PadW4)") (class "Default")
      (node (ref "IC9") (pin "W4") (pinfunction "MGTHTXN1_225_W4") (pintype "output"))
    )
    (net (code "66") (name "unconnected-(IC9H-MGTHTXN1_226-PadL4)") (class "Default")
      (node (ref "IC9") (pin "L4") (pinfunction "MGTHTXN1_226_L4") (pintype "output"))
    )
    (net (code "67") (name "unconnected-(IC9H-MGTHTXN2_224-PadAD6)") (class "Default")
      (node (ref "IC9") (pin "AD6") (pinfunction "MGTHTXN2_224_AD6") (pintype "output"))
    )
    (net (code "68") (name "unconnected-(IC9H-MGTHTXN2_225-PadU4)") (class "Default")
      (node (ref "IC9") (pin "U4") (pinfunction "MGTHTXN2_225_U4") (pintype "output"))
    )
    (net (code "69") (name "unconnected-(IC9H-MGTHTXN2_226-PadJ4)") (class "Default")
      (node (ref "IC9") (pin "J4") (pinfunction "MGTHTXN2_226_J4") (pintype "output"))
    )
    (net (code "70") (name "unconnected-(IC9H-MGTHTXN3_224-PadAC4)") (class "Default")
      (node (ref "IC9") (pin "AC4") (pinfunction "MGTHTXN3_224_AC4") (pintype "output"))
    )
    (net (code "71") (name "unconnected-(IC9H-MGTHTXN3_225-PadR4)") (class "Default")
      (node (ref "IC9") (pin "R4") (pinfunction "MGTHTXN3_225_R4") (pintype "output"))
    )
    (net (code "72") (name "unconnected-(IC9H-MGTHTXN3_226-PadG4)") (class "Default")
      (node (ref "IC9") (pin "G4") (pinfunction "MGTHTXN3_226_G4") (pintype "output"))
    )
    (net (code "73") (name "unconnected-(IC9H-MGTHTXP0_224-PadAF7)") (class "Default")
      (node (ref "IC9") (pin "AF7") (pinfunction "MGTHTXP0_224_AF7") (pintype "output"))
    )
    (net (code "74") (name "unconnected-(IC9H-MGTHTXP0_225-PadAA5)") (class "Default")
      (node (ref "IC9") (pin "AA5") (pinfunction "MGTHTXP0_225_AA5") (pintype "output"))
    )
    (net (code "75") (name "unconnected-(IC9H-MGTHTXP0_226-PadN5)") (class "Default")
      (node (ref "IC9") (pin "N5") (pinfunction "MGTHTXP0_226_N5") (pintype "output"))
    )
    (net (code "76") (name "unconnected-(IC9H-MGTHTXP1_224-PadAE9)") (class "Default")
      (node (ref "IC9") (pin "AE9") (pinfunction "MGTHTXP1_224_AE9") (pintype "output"))
    )
    (net (code "77") (name "unconnected-(IC9H-MGTHTXP1_225-PadW5)") (class "Default")
      (node (ref "IC9") (pin "W5") (pinfunction "MGTHTXP1_225_W5") (pintype "output"))
    )
    (net (code "78") (name "unconnected-(IC9H-MGTHTXP1_226-PadL5)") (class "Default")
      (node (ref "IC9") (pin "L5") (pinfunction "MGTHTXP1_226_L5") (pintype "output"))
    )
    (net (code "79") (name "unconnected-(IC9H-MGTHTXP2_224-PadAD7)") (class "Default")
      (node (ref "IC9") (pin "AD7") (pinfunction "MGTHTXP2_224_AD7") (pintype "output"))
    )
    (net (code "80") (name "unconnected-(IC9H-MGTHTXP2_225-PadU5)") (class "Default")
      (node (ref "IC9") (pin "U5") (pinfunction "MGTHTXP2_225_U5") (pintype "output"))
    )
    (net (code "81") (name "unconnected-(IC9H-MGTHTXP2_226-PadJ5)") (class "Default")
      (node (ref "IC9") (pin "J5") (pinfunction "MGTHTXP2_226_J5") (pintype "output"))
    )
    (net (code "82") (name "unconnected-(IC9H-MGTHTXP3_224-PadAC5)") (class "Default")
      (node (ref "IC9") (pin "AC5") (pinfunction "MGTHTXP3_224_AC5") (pintype "output"))
    )
    (net (code "83") (name "unconnected-(IC9H-MGTHTXP3_225-PadR5)") (class "Default")
      (node (ref "IC9") (pin "R5") (pinfunction "MGTHTXP3_225_R5") (pintype "output"))
    )
    (net (code "84") (name "unconnected-(IC9H-MGTHTXP3_226-PadG5)") (class "Default")
      (node (ref "IC9") (pin "G5") (pinfunction "MGTHTXP3_226_G5") (pintype "output"))
    )
    (net (code "85") (name "unconnected-(IC9H-MGTREFCLK0N_224-PadAB6)") (class "Default")
      (node (ref "IC9") (pin "AB6") (pinfunction "MGTREFCLK0N_224_AB6") (pintype "input+no_connect"))
    )
    (net (code "86") (name "unconnected-(IC9H-MGTREFCLK0N_225-PadV6)") (class "Default")
      (node (ref "IC9") (pin "V6") (pinfunction "MGTREFCLK0N_225_V6") (pintype "input+no_connect"))
    )
    (net (code "87") (name "unconnected-(IC9H-MGTREFCLK0N_226-PadP6)") (class "Default")
      (node (ref "IC9") (pin "P6") (pinfunction "MGTREFCLK0N_226_P6") (pintype "input+no_connect"))
    )
    (net (code "88") (name "unconnected-(IC9H-MGTREFCLK0P_224-PadAB7)") (class "Default")
      (node (ref "IC9") (pin "AB7") (pinfunction "MGTREFCLK0P_224_AB7") (pintype "input+no_connect"))
    )
    (net (code "89") (name "unconnected-(IC9H-MGTREFCLK0P_225-PadV7)") (class "Default")
      (node (ref "IC9") (pin "V7") (pinfunction "MGTREFCLK0P_225_V7") (pintype "input+no_connect"))
    )
    (net (code "90") (name "unconnected-(IC9H-MGTREFCLK0P_226-PadP7)") (class "Default")
      (node (ref "IC9") (pin "P7") (pinfunction "MGTREFCLK0P_226_P7") (pintype "input+no_connect"))
    )
    (net (code "91") (name "unconnected-(IC9H-MGTREFCLK1N_224-PadY6)") (class "Default")
      (node (ref "IC9") (pin "Y6") (pinfunction "MGTREFCLK1N_224_Y6") (pintype "input+no_connect"))
    )
    (net (code "92") (name "unconnected-(IC9H-MGTREFCLK1N_225-PadT6)") (class "Default")
      (node (ref "IC9") (pin "T6") (pinfunction "MGTREFCLK1N_225_T6") (pintype "input+no_connect"))
    )
    (net (code "93") (name "unconnected-(IC9H-MGTREFCLK1N_226-PadM6)") (class "Default")
      (node (ref "IC9") (pin "M6") (pinfunction "MGTREFCLK1N_226_M6") (pintype "input+no_connect"))
    )
    (net (code "94") (name "unconnected-(IC9H-MGTREFCLK1P_224-PadY7)") (class "Default")
      (node (ref "IC9") (pin "Y7") (pinfunction "MGTREFCLK1P_224_Y7") (pintype "input+no_connect"))
    )
    (net (code "95") (name "unconnected-(IC9H-MGTREFCLK1P_225-PadT7)") (class "Default")
      (node (ref "IC9") (pin "T7") (pinfunction "MGTREFCLK1P_225_T7") (pintype "input+no_connect"))
    )
    (net (code "96") (name "unconnected-(IC9H-MGTREFCLK1P_226-PadM7)") (class "Default")
      (node (ref "IC9") (pin "M7") (pinfunction "MGTREFCLK1P_226_M7") (pintype "input+no_connect"))
    )
    (net (code "97") (name "unconnected-(IC9I-MGTAVCC_R-PadAA7)") (class "Default")
      (node (ref "IC9") (pin "AA7") (pinfunction "MGTAVCC_R_AA7") (pintype "power_in"))
    )
    (net (code "98") (name "unconnected-(IC9I-MGTAVCC_R-PadAC7)") (class "Default")
      (node (ref "IC9") (pin "AC7") (pinfunction "MGTAVCC_R_AC7") (pintype "power_in"))
    )
    (net (code "99") (name "unconnected-(IC9I-MGTAVCC_R-PadJ7)") (class "Default")
      (node (ref "IC9") (pin "J7") (pinfunction "MGTAVCC_R_J7") (pintype "power_in"))
    )
    (net (code "100") (name "unconnected-(IC9I-MGTAVCC_R-PadL7)") (class "Default")
      (node (ref "IC9") (pin "L7") (pinfunction "MGTAVCC_R_L7") (pintype "power_in"))
    )
    (net (code "101") (name "unconnected-(IC9I-MGTAVCC_R-PadN7)") (class "Default")
      (node (ref "IC9") (pin "N7") (pinfunction "MGTAVCC_R_N7") (pintype "power_in"))
    )
    (net (code "102") (name "unconnected-(IC9I-MGTAVCC_R-PadW7)") (class "Default")
      (node (ref "IC9") (pin "W7") (pinfunction "MGTAVCC_R_W7") (pintype "power_in"))
    )
    (net (code "103") (name "unconnected-(IC9I-MGTAVTT_R-PadA7)") (class "Default")
      (node (ref "IC9") (pin "A7") (pinfunction "MGTAVTT_R_A7") (pintype "power_in"))
    )
    (net (code "104") (name "unconnected-(IC9I-MGTAVTT_R-PadAB5)") (class "Default")
      (node (ref "IC9") (pin "AB5") (pinfunction "MGTAVTT_R_AB5") (pintype "power_in"))
    )
    (net (code "105") (name "unconnected-(IC9I-MGTAVTT_R-PadAE7)") (class "Default")
      (node (ref "IC9") (pin "AE7") (pinfunction "MGTAVTT_R_AE7") (pintype "power_in"))
    )
    (net (code "106") (name "unconnected-(IC9I-MGTAVTT_R-PadC7)") (class "Default")
      (node (ref "IC9") (pin "C7") (pinfunction "MGTAVTT_R_C7") (pintype "power_in"))
    )
    (net (code "107") (name "unconnected-(IC9I-MGTAVTT_R-PadE7)") (class "Default")
      (node (ref "IC9") (pin "E7") (pinfunction "MGTAVTT_R_E7") (pintype "power_in"))
    )
    (net (code "108") (name "unconnected-(IC9I-MGTAVTT_R-PadF5)") (class "Default")
      (node (ref "IC9") (pin "F5") (pinfunction "MGTAVTT_R_F5") (pintype "power_in"))
    )
    (net (code "109") (name "unconnected-(IC9I-MGTAVTT_R-PadG7)") (class "Default")
      (node (ref "IC9") (pin "G7") (pinfunction "MGTAVTT_R_G7") (pintype "power_in"))
    )
    (net (code "110") (name "unconnected-(IC9I-MGTAVTT_R-PadH5)") (class "Default")
      (node (ref "IC9") (pin "H5") (pinfunction "MGTAVTT_R_H5") (pintype "power_in"))
    )
    (net (code "111") (name "unconnected-(IC9I-MGTAVTT_R-PadK5)") (class "Default")
      (node (ref "IC9") (pin "K5") (pinfunction "MGTAVTT_R_K5") (pintype "power_in"))
    )
    (net (code "112") (name "unconnected-(IC9I-MGTAVTT_R-PadM5)") (class "Default")
      (node (ref "IC9") (pin "M5") (pinfunction "MGTAVTT_R_M5") (pintype "power_in"))
    )
    (net (code "113") (name "unconnected-(IC9I-MGTAVTT_R-PadP5)") (class "Default")
      (node (ref "IC9") (pin "P5") (pinfunction "MGTAVTT_R_P5") (pintype "power_in"))
    )
    (net (code "114") (name "unconnected-(IC9I-MGTAVTT_R-PadT5)") (class "Default")
      (node (ref "IC9") (pin "T5") (pinfunction "MGTAVTT_R_T5") (pintype "power_in"))
    )
    (net (code "115") (name "unconnected-(IC9I-MGTAVTT_R-PadV5)") (class "Default")
      (node (ref "IC9") (pin "V5") (pinfunction "MGTAVTT_R_V5") (pintype "power_in"))
    )
    (net (code "116") (name "unconnected-(IC9I-MGTAVTT_R-PadY5)") (class "Default")
      (node (ref "IC9") (pin "Y5") (pinfunction "MGTAVTT_R_Y5") (pintype "power_in"))
    )
    (net (code "117") (name "unconnected-(IC9I-MGTVCCAUX_R-PadR7)") (class "Default")
      (node (ref "IC9") (pin "R7") (pinfunction "MGTVCCAUX_R_R7") (pintype "power_in"))
    )
    (net (code "118") (name "unconnected-(IC9I-MGTVCCAUX_R-PadU7)") (class "Default")
      (node (ref "IC9") (pin "U7") (pinfunction "MGTVCCAUX_R_U7") (pintype "power_in"))
    )
    (net (code "119") (name "unconnected-(IC9K-RSVDGND-PadW11)") (class "Default")
      (node (ref "IC9") (pin "W11") (pinfunction "RSVDGND_W11") (pintype "power_in"))
    )
    (net (code "120") (name "unconnected-(IC9L-NC-PadA3)") (class "Default")
      (node (ref "IC9") (pin "A3") (pinfunction "NC_A3") (pintype "passive"))
    )
    (net (code "121") (name "unconnected-(IC9L-NC-PadA4)") (class "Default")
      (node (ref "IC9") (pin "A4") (pinfunction "NC_A4") (pintype "passive"))
    )
    (net (code "122") (name "unconnected-(IC9L-NC-PadA15)") (class "Default")
      (node (ref "IC9") (pin "A15") (pinfunction "NC_A15") (pintype "passive"))
    )
    (net (code "123") (name "unconnected-(IC9L-NC-PadA17)") (class "Default")
      (node (ref "IC9") (pin "A17") (pinfunction "NC_A17") (pintype "passive"))
    )
    (net (code "124") (name "unconnected-(IC9L-NC-PadA18)") (class "Default")
      (node (ref "IC9") (pin "A18") (pinfunction "NC_A18") (pintype "passive"))
    )
    (net (code "125") (name "unconnected-(IC9L-NC-PadA19)") (class "Default")
      (node (ref "IC9") (pin "A19") (pinfunction "NC_A19") (pintype "passive"))
    )
    (net (code "126") (name "unconnected-(IC9L-NC-PadA20)") (class "Default")
      (node (ref "IC9") (pin "A20") (pinfunction "NC_A20") (pintype "passive"))
    )
    (net (code "127") (name "unconnected-(IC9L-NC-PadA22)") (class "Default")
      (node (ref "IC9") (pin "A22") (pinfunction "NC_A22") (pintype "passive"))
    )
    (net (code "128") (name "unconnected-(IC9L-NC-PadA23)") (class "Default")
      (node (ref "IC9") (pin "A23") (pinfunction "NC_A23") (pintype "passive"))
    )
    (net (code "129") (name "unconnected-(IC9L-NC-PadA24)") (class "Default")
      (node (ref "IC9") (pin "A24") (pinfunction "NC_A24") (pintype "passive"))
    )
    (net (code "130") (name "unconnected-(IC9L-NC-PadA25)") (class "Default")
      (node (ref "IC9") (pin "A25") (pinfunction "NC_A25") (pintype "passive"))
    )
    (net (code "131") (name "unconnected-(IC9L-NC-PadB1)") (class "Default")
      (node (ref "IC9") (pin "B1") (pinfunction "NC_B1") (pintype "passive"))
    )
    (net (code "132") (name "unconnected-(IC9L-NC-PadB2)") (class "Default")
      (node (ref "IC9") (pin "B2") (pinfunction "NC_B2") (pintype "passive"))
    )
    (net (code "133") (name "unconnected-(IC9L-NC-PadB6)") (class "Default")
      (node (ref "IC9") (pin "B6") (pinfunction "NC_B6") (pintype "passive"))
    )
    (net (code "134") (name "unconnected-(IC9L-NC-PadB7)") (class "Default")
      (node (ref "IC9") (pin "B7") (pinfunction "NC_B7") (pintype "passive"))
    )
    (net (code "135") (name "unconnected-(IC9L-NC-PadB15)") (class "Default")
      (node (ref "IC9") (pin "B15") (pinfunction "NC_B15") (pintype "passive"))
    )
    (net (code "136") (name "unconnected-(IC9L-NC-PadB16)") (class "Default")
      (node (ref "IC9") (pin "B16") (pinfunction "NC_B16") (pintype "passive"))
    )
    (net (code "137") (name "unconnected-(IC9L-NC-PadB17)") (class "Default")
      (node (ref "IC9") (pin "B17") (pinfunction "NC_B17") (pintype "passive"))
    )
    (net (code "138") (name "unconnected-(IC9L-NC-PadB19)") (class "Default")
      (node (ref "IC9") (pin "B19") (pinfunction "NC_B19") (pintype "passive"))
    )
    (net (code "139") (name "unconnected-(IC9L-NC-PadB20)") (class "Default")
      (node (ref "IC9") (pin "B20") (pinfunction "NC_B20") (pintype "passive"))
    )
    (net (code "140") (name "unconnected-(IC9L-NC-PadB21)") (class "Default")
      (node (ref "IC9") (pin "B21") (pinfunction "NC_B21") (pintype "passive"))
    )
    (net (code "141") (name "unconnected-(IC9L-NC-PadB22)") (class "Default")
      (node (ref "IC9") (pin "B22") (pinfunction "NC_B22") (pintype "passive"))
    )
    (net (code "142") (name "unconnected-(IC9L-NC-PadB24)") (class "Default")
      (node (ref "IC9") (pin "B24") (pinfunction "NC_B24") (pintype "passive"))
    )
    (net (code "143") (name "unconnected-(IC9L-NC-PadC3)") (class "Default")
      (node (ref "IC9") (pin "C3") (pinfunction "NC_C3") (pintype "passive"))
    )
    (net (code "144") (name "unconnected-(IC9L-NC-PadC4)") (class "Default")
      (node (ref "IC9") (pin "C4") (pinfunction "NC_C4") (pintype "passive"))
    )
    (net (code "145") (name "unconnected-(IC9L-NC-PadC16)") (class "Default")
      (node (ref "IC9") (pin "C16") (pinfunction "NC_C16") (pintype "passive"))
    )
    (net (code "146") (name "unconnected-(IC9L-NC-PadC17)") (class "Default")
      (node (ref "IC9") (pin "C17") (pinfunction "NC_C17") (pintype "passive"))
    )
    (net (code "147") (name "unconnected-(IC9L-NC-PadC18)") (class "Default")
      (node (ref "IC9") (pin "C18") (pinfunction "NC_C18") (pintype "passive"))
    )
    (net (code "148") (name "unconnected-(IC9L-NC-PadC19)") (class "Default")
      (node (ref "IC9") (pin "C19") (pinfunction "NC_C19") (pintype "passive"))
    )
    (net (code "149") (name "unconnected-(IC9L-NC-PadC20)") (class "Default")
      (node (ref "IC9") (pin "C20") (pinfunction "NC_C20") (pintype "passive"))
    )
    (net (code "150") (name "unconnected-(IC9L-NC-PadC21)") (class "Default")
      (node (ref "IC9") (pin "C21") (pinfunction "NC_C21") (pintype "passive"))
    )
    (net (code "151") (name "unconnected-(IC9L-NC-PadC22)") (class "Default")
      (node (ref "IC9") (pin "C22") (pinfunction "NC_C22") (pintype "passive"))
    )
    (net (code "152") (name "unconnected-(IC9L-NC-PadC23)") (class "Default")
      (node (ref "IC9") (pin "C23") (pinfunction "NC_C23") (pintype "passive"))
    )
    (net (code "153") (name "unconnected-(IC9L-NC-PadD1)") (class "Default")
      (node (ref "IC9") (pin "D1") (pinfunction "NC_D1") (pintype "passive"))
    )
    (net (code "154") (name "unconnected-(IC9L-NC-PadD2)") (class "Default")
      (node (ref "IC9") (pin "D2") (pinfunction "NC_D2") (pintype "passive"))
    )
    (net (code "155") (name "unconnected-(IC9L-NC-PadD6)") (class "Default")
      (node (ref "IC9") (pin "D6") (pinfunction "NC_D6") (pintype "passive"))
    )
    (net (code "156") (name "unconnected-(IC9L-NC-PadD7)") (class "Default")
      (node (ref "IC9") (pin "D7") (pinfunction "NC_D7") (pintype "passive"))
    )
    (net (code "157") (name "unconnected-(IC9L-NC-PadD15)") (class "Default")
      (node (ref "IC9") (pin "D15") (pinfunction "NC_D15") (pintype "passive"))
    )
    (net (code "158") (name "unconnected-(IC9L-NC-PadD16)") (class "Default")
      (node (ref "IC9") (pin "D16") (pinfunction "NC_D16") (pintype "passive"))
    )
    (net (code "159") (name "unconnected-(IC9L-NC-PadD17)") (class "Default")
      (node (ref "IC9") (pin "D17") (pinfunction "NC_D17") (pintype "passive"))
    )
    (net (code "160") (name "unconnected-(IC9L-NC-PadD18)") (class "Default")
      (node (ref "IC9") (pin "D18") (pinfunction "NC_D18") (pintype "passive"))
    )
    (net (code "161") (name "unconnected-(IC9L-NC-PadD19)") (class "Default")
      (node (ref "IC9") (pin "D19") (pinfunction "NC_D19") (pintype "passive"))
    )
    (net (code "162") (name "unconnected-(IC9L-NC-PadD20)") (class "Default")
      (node (ref "IC9") (pin "D20") (pinfunction "NC_D20") (pintype "passive"))
    )
    (net (code "163") (name "unconnected-(IC9L-NC-PadD21)") (class "Default")
      (node (ref "IC9") (pin "D21") (pinfunction "NC_D21") (pintype "passive"))
    )
    (net (code "164") (name "unconnected-(IC9L-NC-PadE4)") (class "Default")
      (node (ref "IC9") (pin "E4") (pinfunction "NC_E4") (pintype "passive"))
    )
    (net (code "165") (name "unconnected-(IC9L-NC-PadE5)") (class "Default")
      (node (ref "IC9") (pin "E5") (pinfunction "NC_E5") (pintype "passive"))
    )
    (net (code "166") (name "unconnected-(IC9L-NC-PadE15)") (class "Default")
      (node (ref "IC9") (pin "E15") (pinfunction "NC_E15") (pintype "passive"))
    )
    (net (code "167") (name "unconnected-(IC9L-NC-PadE16)") (class "Default")
      (node (ref "IC9") (pin "E16") (pinfunction "NC_E16") (pintype "passive"))
    )
    (net (code "168") (name "unconnected-(IC9L-NC-PadE17)") (class "Default")
      (node (ref "IC9") (pin "E17") (pinfunction "NC_E17") (pintype "passive"))
    )
    (net (code "169") (name "unconnected-(IC9L-NC-PadE18)") (class "Default")
      (node (ref "IC9") (pin "E18") (pinfunction "NC_E18") (pintype "passive"))
    )
    (net (code "170") (name "unconnected-(IC9L-NC-PadE20)") (class "Default")
      (node (ref "IC9") (pin "E20") (pinfunction "NC_E20") (pintype "passive"))
    )
    (net (code "171") (name "unconnected-(IC9L-NC-PadE21)") (class "Default")
      (node (ref "IC9") (pin "E21") (pinfunction "NC_E21") (pintype "passive"))
    )
    (net (code "172") (name "unconnected-(IC9L-NC-PadE22)") (class "Default")
      (node (ref "IC9") (pin "E22") (pinfunction "NC_E22") (pintype "passive"))
    )
    (net (code "173") (name "unconnected-(IC9L-NC-PadF6)") (class "Default")
      (node (ref "IC9") (pin "F6") (pinfunction "NC_F6") (pintype "passive"))
    )
    (net (code "174") (name "unconnected-(IC9L-NC-PadF7)") (class "Default")
      (node (ref "IC9") (pin "F7") (pinfunction "NC_F7") (pintype "passive"))
    )
    (net (code "175") (name "unconnected-(IC9L-NC-PadF15)") (class "Default")
      (node (ref "IC9") (pin "F15") (pinfunction "NC_F15") (pintype "passive"))
    )
    (net (code "176") (name "unconnected-(IC9L-NC-PadF17)") (class "Default")
      (node (ref "IC9") (pin "F17") (pinfunction "NC_F17") (pintype "passive"))
    )
    (net (code "177") (name "unconnected-(IC9L-NC-PadF18)") (class "Default")
      (node (ref "IC9") (pin "F18") (pinfunction "NC_F18") (pintype "passive"))
    )
    (net (code "178") (name "unconnected-(IC9L-NC-PadF19)") (class "Default")
      (node (ref "IC9") (pin "F19") (pinfunction "NC_F19") (pintype "passive"))
    )
    (net (code "179") (name "unconnected-(IC9L-NC-PadF20)") (class "Default")
      (node (ref "IC9") (pin "F20") (pinfunction "NC_F20") (pintype "passive"))
    )
    (net (code "180") (name "unconnected-(IC9L-NC-PadG15)") (class "Default")
      (node (ref "IC9") (pin "G15") (pinfunction "NC_G15") (pintype "passive"))
    )
    (net (code "181") (name "unconnected-(IC9L-NC-PadG16)") (class "Default")
      (node (ref "IC9") (pin "G16") (pinfunction "NC_G16") (pintype "passive"))
    )
    (net (code "182") (name "unconnected-(IC9L-NC-PadG17)") (class "Default")
      (node (ref "IC9") (pin "G17") (pinfunction "NC_G17") (pintype "passive"))
    )
    (net (code "183") (name "unconnected-(IC9L-NC-PadG18)") (class "Default")
      (node (ref "IC9") (pin "G18") (pinfunction "NC_G18") (pintype "passive"))
    )
    (net (code "184") (name "unconnected-(IC9L-NC-PadG19)") (class "Default")
      (node (ref "IC9") (pin "G19") (pinfunction "NC_G19") (pintype "passive"))
    )
    (net (code "185") (name "unconnected-(IC9L-NC-PadG20)") (class "Default")
      (node (ref "IC9") (pin "G20") (pinfunction "NC_G20") (pintype "passive"))
    )
    (net (code "186") (name "unconnected-(IC9L-NC-PadG21)") (class "Default")
      (node (ref "IC9") (pin "G21") (pinfunction "NC_G21") (pintype "passive"))
    )
    (net (code "187") (name "unconnected-(IC9L-NC-PadH6)") (class "Default")
      (node (ref "IC9") (pin "H6") (pinfunction "NC_H6") (pintype "passive"))
    )
    (net (code "188") (name "unconnected-(IC9L-NC-PadH7)") (class "Default")
      (node (ref "IC9") (pin "H7") (pinfunction "NC_H7") (pintype "passive"))
    )
    (net (code "189") (name "unconnected-(IC9L-NC-PadH16)") (class "Default")
      (node (ref "IC9") (pin "H16") (pinfunction "NC_H16") (pintype "passive"))
    )
    (net (code "190") (name "unconnected-(IC9L-NC-PadH17)") (class "Default")
      (node (ref "IC9") (pin "H17") (pinfunction "NC_H17") (pintype "passive"))
    )
    (net (code "191") (name "unconnected-(IC9L-NC-PadH18)") (class "Default")
      (node (ref "IC9") (pin "H18") (pinfunction "NC_H18") (pintype "passive"))
    )
    (net (code "192") (name "unconnected-(IC9L-NC-PadH19)") (class "Default")
      (node (ref "IC9") (pin "H19") (pinfunction "NC_H19") (pintype "passive"))
    )
    (net (code "193") (name "unconnected-(IC9L-NC-PadJ16)") (class "Default")
      (node (ref "IC9") (pin "J16") (pinfunction "NC_J16") (pintype "passive"))
    )
    (net (code "194") (name "unconnected-(IC9L-NC-PadK6)") (class "Default")
      (node (ref "IC9") (pin "K6") (pinfunction "NC_K6") (pintype "passive"))
    )
    (net (code "195") (name "unconnected-(IC9L-NC-PadK7)") (class "Default")
      (node (ref "IC9") (pin "K7") (pinfunction "NC_K7") (pintype "passive"))
    )
    (net (code "196") (name "unconnected-(IC18-DNU-Pad4)") (class "Default")
      (node (ref "IC18") (pin "4") (pinfunction "DNU_4") (pintype "passive+no_connect"))
    )
    (net (code "197") (name "unconnected-(IC18-DNU-Pad5)") (class "Default")
      (node (ref "IC18") (pin "5") (pinfunction "DNU_5") (pintype "passive+no_connect"))
    )
    (net (code "198") (name "unconnected-(IC18-DNU-Pad6)") (class "Default")
      (node (ref "IC18") (pin "6") (pinfunction "DNU_6") (pintype "passive+no_connect"))
    )
    (net (code "199") (name "unconnected-(IC18-DNU-Pad11)") (class "Default")
      (node (ref "IC18") (pin "11") (pinfunction "DNU_11") (pintype "passive+no_connect"))
    )
    (net (code "200") (name "unconnected-(IC18-DNU-Pad12)") (class "Default")
      (node (ref "IC18") (pin "12") (pinfunction "DNU_12") (pintype "passive+no_connect"))
    )
    (net (code "201") (name "unconnected-(IC18-DNU-Pad13)") (class "Default")
      (node (ref "IC18") (pin "13") (pinfunction "DNU_13") (pintype "passive+no_connect"))
    )
    (net (code "202") (name "unconnected-(IC18-DNU-Pad14)") (class "Default")
      (node (ref "IC18") (pin "14") (pinfunction "DNU_14") (pintype "passive+no_connect"))
    )
    (net (code "203") (name "unconnected-(J3-Pad12)") (class "Default")
      (node (ref "J3") (pin "12") (pinfunction "12_12") (pintype "bidirectional+no_connect"))
    )
  )
)
